# GENN0006_LED_INDICATORS.net
KiCad netlist of a schematic drawn in Altium Designer
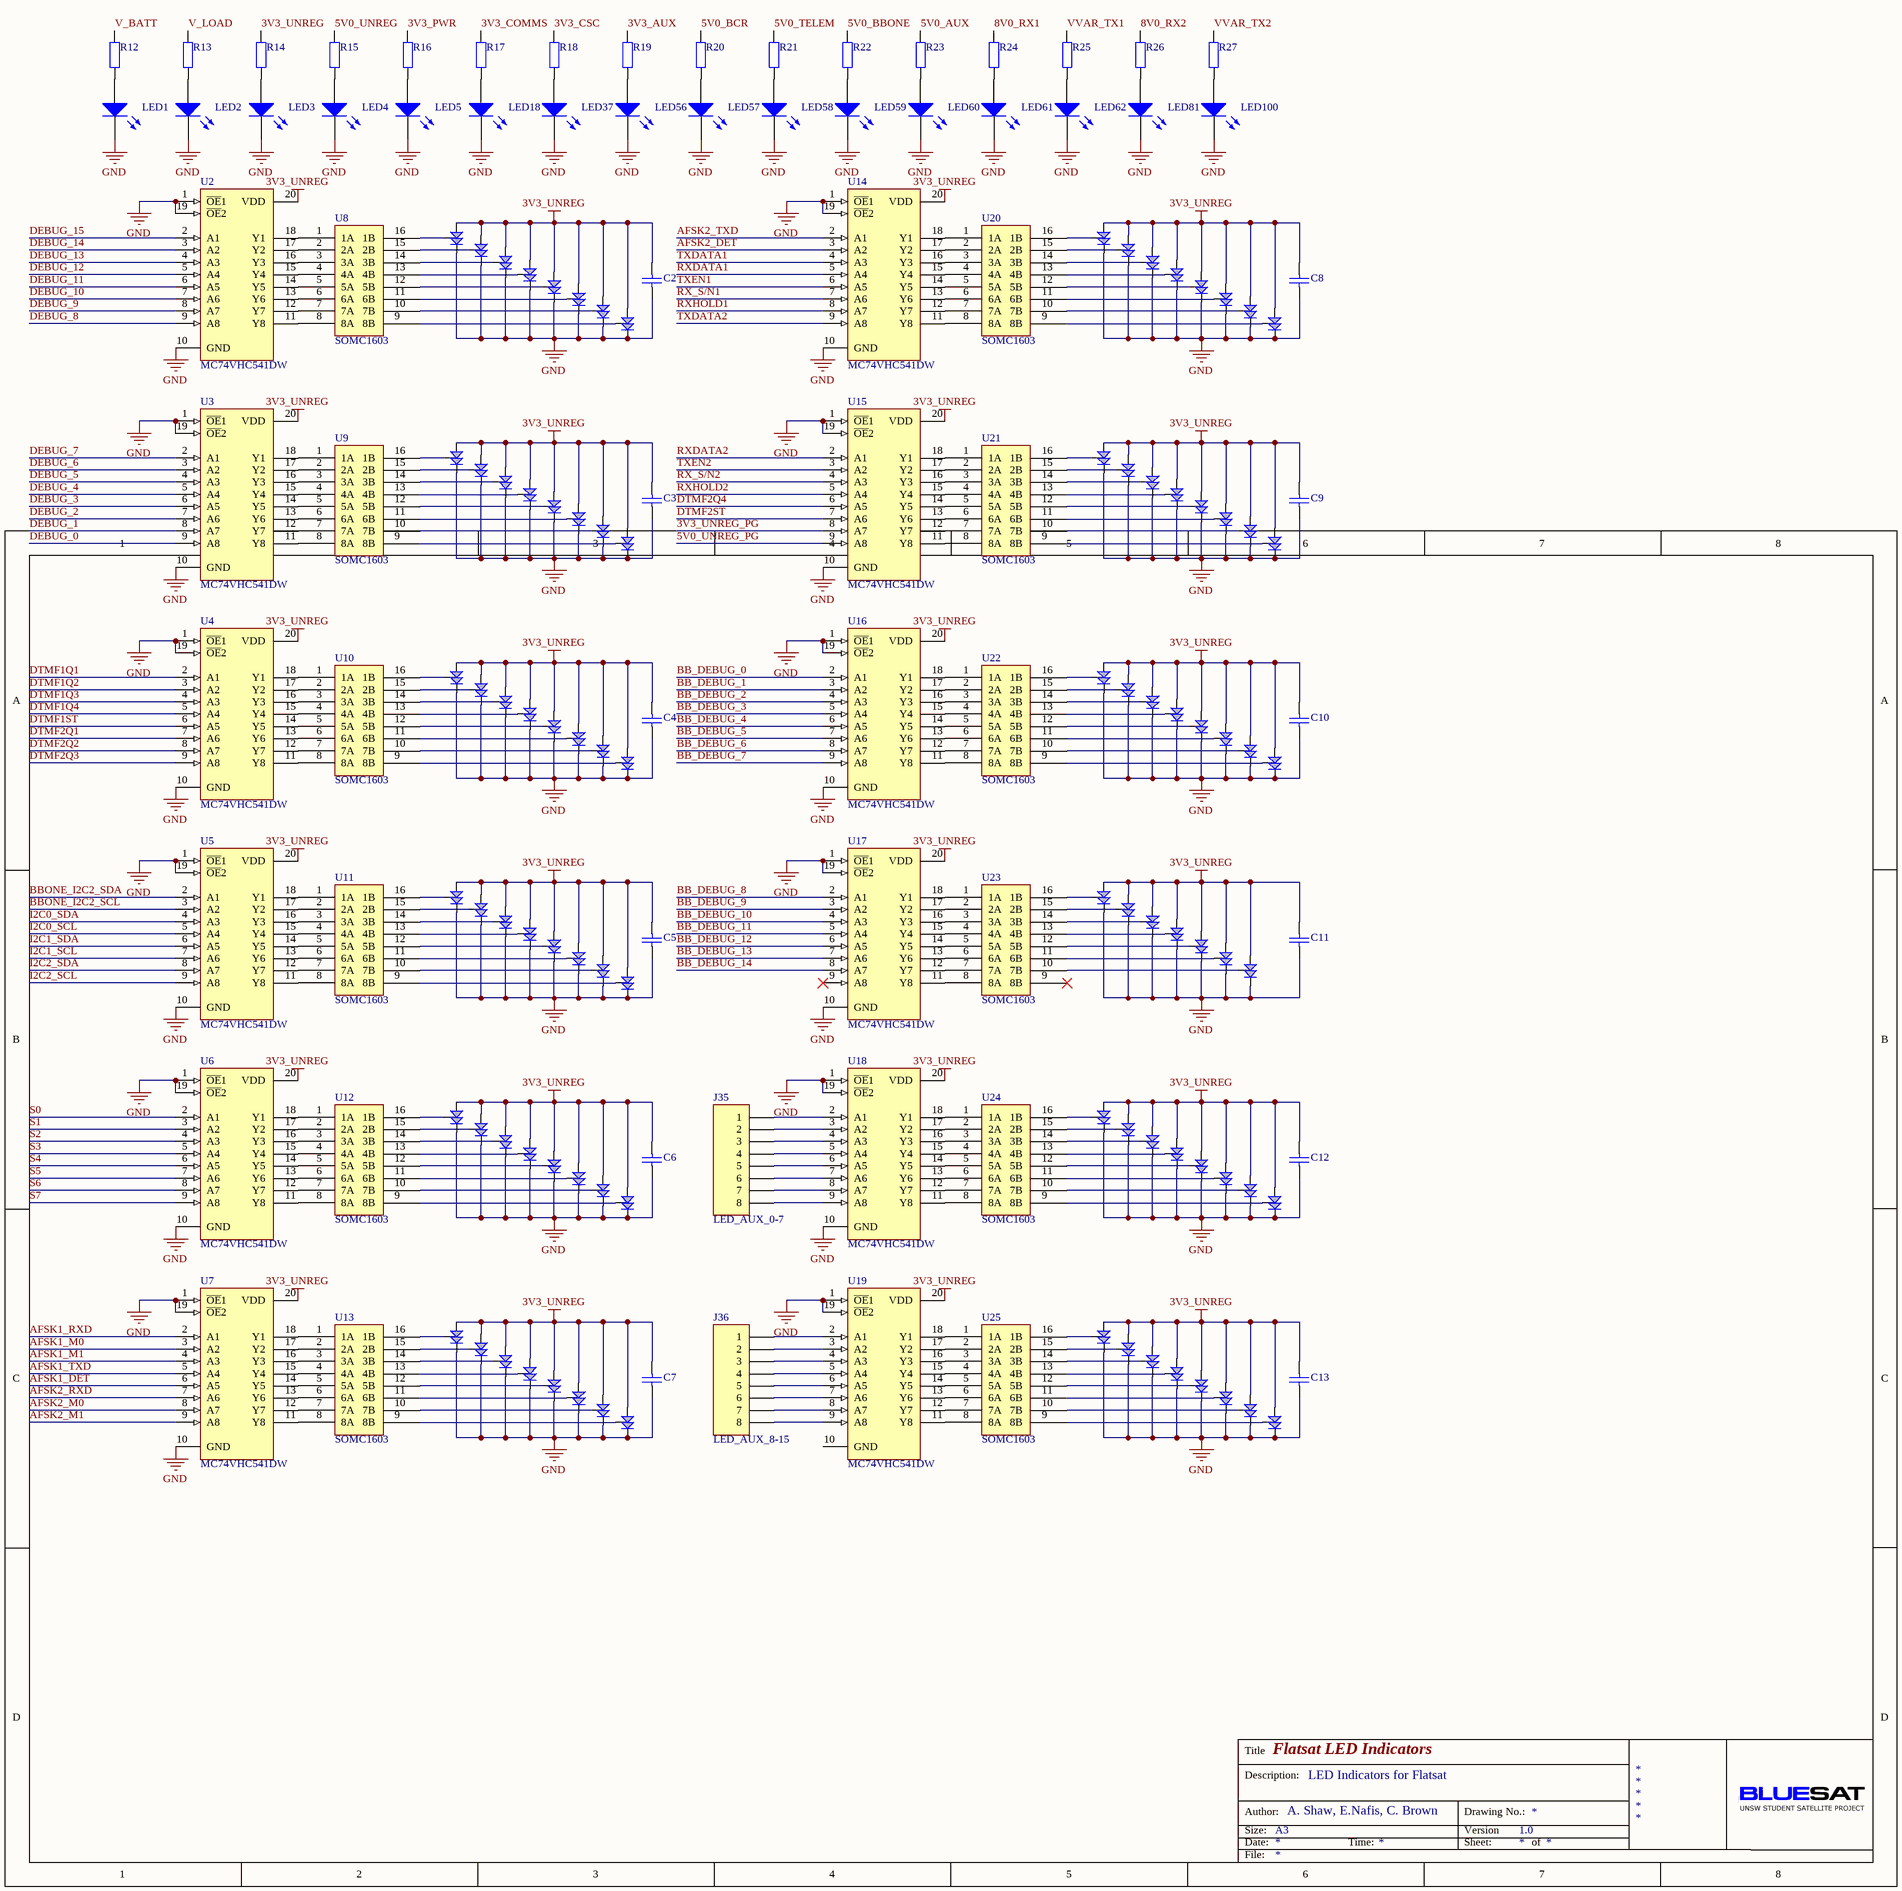
[diagram p0: GENN0006 LED_INDICATORS.SchDoc]

(export (version "E")
  (design (tool "Eeschema 10.0.6"))
  (components
    (comp (ref "C2")
      (value "~")
      (footprint "6-0805_M")
      (description "Capacitor")
      (fields (field (name "PUBLISHER") "Altium Limited"))
      (libsource (lib "Miscellaneous Devices") (part "Cap"))
    )
    (comp (ref "C3")
      (value "~")
      (footprint "6-0805_M")
      (description "Capacitor")
      (fields (field (name "PUBLISHER") "Altium Limited"))
      (libsource (lib "Miscellaneous Devices") (part "Cap"))
    )
    (comp (ref "C4")
      (value "~")
      (footprint "6-0805_M")
      (description "Capacitor")
      (fields (field (name "PUBLISHER") "Altium Limited"))
      (libsource (lib "Miscellaneous Devices") (part "Cap"))
    )
    (comp (ref "C5")
      (value "~")
      (footprint "6-0805_M")
      (description "Capacitor")
      (fields (field (name "PUBLISHER") "Altium Limited"))
      (libsource (lib "Miscellaneous Devices") (part "Cap"))
    )
    (comp (ref "C6")
      (value "~")
      (footprint "6-0805_M")
      (description "Capacitor")
      (fields (field (name "PUBLISHER") "Altium Limited"))
      (libsource (lib "Miscellaneous Devices") (part "Cap"))
    )
    (comp (ref "C7")
      (value "~")
      (footprint "6-0805_M")
      (description "Capacitor")
      (fields (field (name "PUBLISHER") "Altium Limited"))
      (libsource (lib "Miscellaneous Devices") (part "Cap"))
    )
    (comp (ref "C8")
      (value "~")
      (footprint "6-0805_M")
      (description "Capacitor")
      (fields (field (name "PUBLISHER") "Altium Limited"))
      (libsource (lib "Miscellaneous Devices") (part "Cap"))
    )
    (comp (ref "C9")
      (value "~")
      (footprint "6-0805_M")
      (description "Capacitor")
      (fields (field (name "PUBLISHER") "Altium Limited"))
      (libsource (lib "Miscellaneous Devices") (part "Cap"))
    )
    (comp (ref "C10")
      (value "~")
      (footprint "6-0805_M")
      (description "Capacitor")
      (fields (field (name "PUBLISHER") "Altium Limited"))
      (libsource (lib "Miscellaneous Devices") (part "Cap"))
    )
    (comp (ref "C11")
      (value "~")
      (footprint "6-0805_M")
      (description "Capacitor")
      (fields (field (name "PUBLISHER") "Altium Limited"))
      (libsource (lib "Miscellaneous Devices") (part "Cap"))
    )
    (comp (ref "C12")
      (value "~")
      (footprint "6-0805_M")
      (description "Capacitor")
      (fields (field (name "PUBLISHER") "Altium Limited"))
      (libsource (lib "Miscellaneous Devices") (part "Cap"))
    )
    (comp (ref "C13")
      (value "~")
      (footprint "6-0805_M")
      (description "Capacitor")
      (fields (field (name "PUBLISHER") "Altium Limited"))
      (libsource (lib "Miscellaneous Devices") (part "Cap"))
    )
    (comp (ref "J35")
      (value "LED_AUX_0-7")
      (footprint "HDR1X8")
      (description "Header, 8-Pin")
      (fields (field (name "PUBLISHER") "Altium Limited"))
      (libsource (lib "Miscellaneous Connectors") (part "Header 8"))
    )
    (comp (ref "J36")
      (value "LED_AUX_8-15")
      (footprint "HDR1X8")
      (description "Header, 8-Pin")
      (fields (field (name "PUBLISHER") "Altium Limited"))
      (libsource (lib "Miscellaneous Connectors") (part "Header 8"))
    )
    (comp (ref "LED1")
      (value "V_BATT")
      (footprint "6-0805_M")
      (description "Typical INFRARED GaAs LED")
      (fields (field (name "PUBLISHER") "Altium Limited"))
      (libsource (lib "Miscellaneous Devices") (part "LED0"))
    )
    (comp (ref "LED2")
      (value "V_LOAD")
      (footprint "6-0805_M")
      (description "Typical INFRARED GaAs LED")
      (fields (field (name "PUBLISHER") "Altium Limited"))
      (libsource (lib "Miscellaneous Devices") (part "LED0"))
    )
    (comp (ref "LED3")
      (value "3V3_UNREG")
      (footprint "6-0805_M")
      (description "Typical INFRARED GaAs LED")
      (fields (field (name "PUBLISHER") "Altium Limited"))
      (libsource (lib "Miscellaneous Devices") (part "LED0"))
    )
    (comp (ref "LED4")
      (value "5V0_UNREG")
      (footprint "6-0805_M")
      (description "Typical INFRARED GaAs LED")
      (fields (field (name "PUBLISHER") "Altium Limited"))
      (libsource (lib "Miscellaneous Devices") (part "LED0"))
    )
    (comp (ref "LED5")
      (value "3V3_PWR")
      (footprint "6-0805_M")
      (description "Typical INFRARED GaAs LED")
      (fields (field (name "PUBLISHER") "Altium Limited"))
      (libsource (lib "Miscellaneous Devices") (part "LED0"))
    )
    (comp (ref "LED6")
      (value "DEBUG_15")
      (footprint "BIDIRECTIONAL LED")
      (libsource (lib "FlatBoards") (part "BIDIRECTIONAL LED"))
    )
    (comp (ref "LED7")
      (value "DEBUG_7")
      (footprint "BIDIRECTIONAL LED")
      (libsource (lib "FlatBoards") (part "BIDIRECTIONAL LED"))
    )
    (comp (ref "LED8")
      (value "DTMF1Q1")
      (footprint "BIDIRECTIONAL LED")
      (libsource (lib "FlatBoards") (part "BIDIRECTIONAL LED"))
    )
    (comp (ref "LED9")
      (value "DTMF2Q4")
      (footprint "BIDIRECTIONAL LED")
      (libsource (lib "FlatBoards") (part "BIDIRECTIONAL LED"))
    )
    (comp (ref "LED10")
      (value "S0")
      (footprint "BIDIRECTIONAL LED")
      (libsource (lib "FlatBoards") (part "BIDIRECTIONAL LED"))
    )
    (comp (ref "LED11")
      (value "AFSK1_RXD")
      (footprint "BIDIRECTIONAL LED")
      (libsource (lib "FlatBoards") (part "BIDIRECTIONAL LED"))
    )
    (comp (ref "LED12")
      (value "DEBUG_14")
      (footprint "BIDIRECTIONAL LED")
      (libsource (lib "FlatBoards") (part "BIDIRECTIONAL LED"))
    )
    (comp (ref "LED13")
      (value "DEBUG_6")
      (footprint "BIDIRECTIONAL LED")
      (libsource (lib "FlatBoards") (part "BIDIRECTIONAL LED"))
    )
    (comp (ref "LED14")
      (value "DTMF1Q2")
      (footprint "BIDIRECTIONAL LED")
      (libsource (lib "FlatBoards") (part "BIDIRECTIONAL LED"))
    )
    (comp (ref "LED15")
      (value "DTMF2ST")
      (footprint "BIDIRECTIONAL LED")
      (libsource (lib "FlatBoards") (part "BIDIRECTIONAL LED"))
    )
    (comp (ref "LED16")
      (value "S1")
      (footprint "BIDIRECTIONAL LED")
      (libsource (lib "FlatBoards") (part "BIDIRECTIONAL LED"))
    )
    (comp (ref "LED17")
      (value "AFSK1_M0")
      (footprint "BIDIRECTIONAL LED")
      (libsource (lib "FlatBoards") (part "BIDIRECTIONAL LED"))
    )
    (comp (ref "LED18")
      (value "3V3_COMMS")
      (footprint "6-0805_M")
      (description "Typical INFRARED GaAs LED")
      (fields (field (name "PUBLISHER") "Altium Limited"))
      (libsource (lib "Miscellaneous Devices") (part "LED0"))
    )
    (comp (ref "LED19")
      (value "DEBUG_13")
      (footprint "BIDIRECTIONAL LED")
      (libsource (lib "FlatBoards") (part "BIDIRECTIONAL LED"))
    )
    (comp (ref "LED20")
      (value "DEBUG_5")
      (footprint "BIDIRECTIONAL LED")
      (libsource (lib "FlatBoards") (part "BIDIRECTIONAL LED"))
    )
    (comp (ref "LED21")
      (value "DTMF1Q3")
      (footprint "BIDIRECTIONAL LED")
      (libsource (lib "FlatBoards") (part "BIDIRECTIONAL LED"))
    )
    (comp (ref "LED22")
      (value "I2C0_SDA")
      (footprint "BIDIRECTIONAL LED")
      (libsource (lib "FlatBoards") (part "BIDIRECTIONAL LED"))
    )
    (comp (ref "LED23")
      (value "S2")
      (footprint "BIDIRECTIONAL LED")
      (libsource (lib "FlatBoards") (part "BIDIRECTIONAL LED"))
    )
    (comp (ref "LED24")
      (value "AFSK1_M1")
      (footprint "BIDIRECTIONAL LED")
      (libsource (lib "FlatBoards") (part "BIDIRECTIONAL LED"))
    )
    (comp (ref "LED25")
      (value "DEBUG_12")
      (footprint "BIDIRECTIONAL LED")
      (libsource (lib "FlatBoards") (part "BIDIRECTIONAL LED"))
    )
    (comp (ref "LED26")
      (value "DEBUG_4")
      (footprint "BIDIRECTIONAL LED")
      (libsource (lib "FlatBoards") (part "BIDIRECTIONAL LED"))
    )
    (comp (ref "LED27")
      (value "DTMF1Q4")
      (footprint "BIDIRECTIONAL LED")
      (libsource (lib "FlatBoards") (part "BIDIRECTIONAL LED"))
    )
    (comp (ref "LED28")
      (value "I2C0_SCL")
      (footprint "BIDIRECTIONAL LED")
      (libsource (lib "FlatBoards") (part "BIDIRECTIONAL LED"))
    )
    (comp (ref "LED29")
      (value "S3")
      (footprint "BIDIRECTIONAL LED")
      (libsource (lib "FlatBoards") (part "BIDIRECTIONAL LED"))
    )
    (comp (ref "LED30")
      (value "AFSK1_TXD")
      (footprint "BIDIRECTIONAL LED")
      (libsource (lib "FlatBoards") (part "BIDIRECTIONAL LED"))
    )
    (comp (ref "LED31")
      (value "DEBUG_11")
      (footprint "BIDIRECTIONAL LED")
      (libsource (lib "FlatBoards") (part "BIDIRECTIONAL LED"))
    )
    (comp (ref "LED32")
      (value "DEBUG_3")
      (footprint "BIDIRECTIONAL LED")
      (libsource (lib "FlatBoards") (part "BIDIRECTIONAL LED"))
    )
    (comp (ref "LED33")
      (value "DTMF1ST")
      (footprint "BIDIRECTIONAL LED")
      (libsource (lib "FlatBoards") (part "BIDIRECTIONAL LED"))
    )
    (comp (ref "LED34")
      (value "I2C1_SDA")
      (footprint "BIDIRECTIONAL LED")
      (libsource (lib "FlatBoards") (part "BIDIRECTIONAL LED"))
    )
    (comp (ref "LED35")
      (value "S4")
      (footprint "BIDIRECTIONAL LED")
      (libsource (lib "FlatBoards") (part "BIDIRECTIONAL LED"))
    )
    (comp (ref "LED36")
      (value "AFSK1_DET")
      (footprint "BIDIRECTIONAL LED")
      (libsource (lib "FlatBoards") (part "BIDIRECTIONAL LED"))
    )
    (comp (ref "LED37")
      (value "3V3_CSC")
      (footprint "6-0805_M")
      (description "Typical INFRARED GaAs LED")
      (fields (field (name "PUBLISHER") "Altium Limited"))
      (libsource (lib "Miscellaneous Devices") (part "LED0"))
    )
    (comp (ref "LED38")
      (value "DEBUG_10")
      (footprint "BIDIRECTIONAL LED")
      (libsource (lib "FlatBoards") (part "BIDIRECTIONAL LED"))
    )
    (comp (ref "LED39")
      (value "DEBUG_2")
      (footprint "BIDIRECTIONAL LED")
      (libsource (lib "FlatBoards") (part "BIDIRECTIONAL LED"))
    )
    (comp (ref "LED40")
      (value "DTMF2Q1")
      (footprint "BIDIRECTIONAL LED")
      (libsource (lib "FlatBoards") (part "BIDIRECTIONAL LED"))
    )
    (comp (ref "LED41")
      (value "I2C1_SCL")
      (footprint "BIDIRECTIONAL LED")
      (libsource (lib "FlatBoards") (part "BIDIRECTIONAL LED"))
    )
    (comp (ref "LED42")
      (value "S5")
      (footprint "BIDIRECTIONAL LED")
      (libsource (lib "FlatBoards") (part "BIDIRECTIONAL LED"))
    )
    (comp (ref "LED43")
      (value "AFSK2_RXD")
      (footprint "BIDIRECTIONAL LED")
      (libsource (lib "FlatBoards") (part "BIDIRECTIONAL LED"))
    )
    (comp (ref "LED44")
      (value "DEBUG_9")
      (footprint "BIDIRECTIONAL LED")
      (libsource (lib "FlatBoards") (part "BIDIRECTIONAL LED"))
    )
    (comp (ref "LED45")
      (value "DEBUG_1")
      (footprint "BIDIRECTIONAL LED")
      (libsource (lib "FlatBoards") (part "BIDIRECTIONAL LED"))
    )
    (comp (ref "LED46")
      (value "DTMF2Q2")
      (footprint "BIDIRECTIONAL LED")
      (libsource (lib "FlatBoards") (part "BIDIRECTIONAL LED"))
    )
    (comp (ref "LED47")
      (value "I2C2_SDA")
      (footprint "BIDIRECTIONAL LED")
      (libsource (lib "FlatBoards") (part "BIDIRECTIONAL LED"))
    )
    (comp (ref "LED48")
      (value "S6")
      (footprint "BIDIRECTIONAL LED")
      (libsource (lib "FlatBoards") (part "BIDIRECTIONAL LED"))
    )
    (comp (ref "LED49")
      (value "AFSK2_M0")
      (footprint "BIDIRECTIONAL LED")
      (libsource (lib "FlatBoards") (part "BIDIRECTIONAL LED"))
    )
    (comp (ref "LED50")
      (value "DEBUG_8")
      (footprint "BIDIRECTIONAL LED")
      (libsource (lib "FlatBoards") (part "BIDIRECTIONAL LED"))
    )
    (comp (ref "LED51")
      (value "DEBUG_0")
      (footprint "BIDIRECTIONAL LED")
      (libsource (lib "FlatBoards") (part "BIDIRECTIONAL LED"))
    )
    (comp (ref "LED52")
      (value "DTMF2Q3")
      (footprint "BIDIRECTIONAL LED")
      (libsource (lib "FlatBoards") (part "BIDIRECTIONAL LED"))
    )
    (comp (ref "LED53")
      (value "I2C2_SCL")
      (footprint "BIDIRECTIONAL LED")
      (libsource (lib "FlatBoards") (part "BIDIRECTIONAL LED"))
    )
    (comp (ref "LED54")
      (value "S7")
      (footprint "BIDIRECTIONAL LED")
      (libsource (lib "FlatBoards") (part "BIDIRECTIONAL LED"))
    )
    (comp (ref "LED55")
      (value "AFSK2_M1")
      (footprint "BIDIRECTIONAL LED")
      (libsource (lib "FlatBoards") (part "BIDIRECTIONAL LED"))
    )
    (comp (ref "LED56")
      (value "3V3_AUX")
      (footprint "6-0805_M")
      (description "Typical INFRARED GaAs LED")
      (fields (field (name "PUBLISHER") "Altium Limited"))
      (libsource (lib "Miscellaneous Devices") (part "LED0"))
    )
    (comp (ref "LED57")
      (value "5V0_BCR")
      (footprint "6-0805_M")
      (description "Typical INFRARED GaAs LED")
      (fields (field (name "PUBLISHER") "Altium Limited"))
      (libsource (lib "Miscellaneous Devices") (part "LED0"))
    )
    (comp (ref "LED58")
      (value "5V0_TELEM")
      (footprint "6-0805_M")
      (description "Typical INFRARED GaAs LED")
      (fields (field (name "PUBLISHER") "Altium Limited"))
      (libsource (lib "Miscellaneous Devices") (part "LED0"))
    )
    (comp (ref "LED59")
      (value "5V0_BBONE")
      (footprint "6-0805_M")
      (description "Typical INFRARED GaAs LED")
      (fields (field (name "PUBLISHER") "Altium Limited"))
      (libsource (lib "Miscellaneous Devices") (part "LED0"))
    )
    (comp (ref "LED60")
      (value "5V0_AUX")
      (footprint "6-0805_M")
      (description "Typical INFRARED GaAs LED")
      (fields (field (name "PUBLISHER") "Altium Limited"))
      (libsource (lib "Miscellaneous Devices") (part "LED0"))
    )
    (comp (ref "LED61")
      (value "8V0_RX1")
      (footprint "6-0805_M")
      (description "Typical INFRARED GaAs LED")
      (fields (field (name "PUBLISHER") "Altium Limited"))
      (libsource (lib "Miscellaneous Devices") (part "LED0"))
    )
    (comp (ref "LED62")
      (value "VVAR_TX1")
      (footprint "6-0805_M")
      (description "Typical INFRARED GaAs LED")
      (fields (field (name "PUBLISHER") "Altium Limited"))
      (libsource (lib "Miscellaneous Devices") (part "LED0"))
    )
    (comp (ref "LED63")
      (value "AFSK2_TXD")
      (footprint "BIDIRECTIONAL LED")
      (libsource (lib "FlatBoards") (part "BIDIRECTIONAL LED"))
    )
    (comp (ref "LED64")
      (value "RXDATA2")
      (footprint "BIDIRECTIONAL LED")
      (libsource (lib "FlatBoards") (part "BIDIRECTIONAL LED"))
    )
    (comp (ref "LED65")
      (value "BB_DEBUG_0")
      (footprint "BIDIRECTIONAL LED")
      (libsource (lib "FlatBoards") (part "BIDIRECTIONAL LED"))
    )
    (comp (ref "LED66")
      (value "BB_DEBUG_8")
      (footprint "BIDIRECTIONAL LED")
      (libsource (lib "FlatBoards") (part "BIDIRECTIONAL LED"))
    )
    (comp (ref "LED67")
      (value "LED_AUX_0")
      (footprint "BIDIRECTIONAL LED")
      (libsource (lib "FlatBoards") (part "BIDIRECTIONAL LED"))
    )
    (comp (ref "LED68")
      (value "LED_AUX_8")
      (footprint "BIDIRECTIONAL LED")
      (libsource (lib "FlatBoards") (part "BIDIRECTIONAL LED"))
    )
    (comp (ref "LED69")
      (value "AFSK2_DET")
      (footprint "BIDIRECTIONAL LED")
      (libsource (lib "FlatBoards") (part "BIDIRECTIONAL LED"))
    )
    (comp (ref "LED70")
      (value "TXEN2")
      (footprint "BIDIRECTIONAL LED")
      (libsource (lib "FlatBoards") (part "BIDIRECTIONAL LED"))
    )
    (comp (ref "LED71")
      (value "BB_DEBUG_1")
      (footprint "BIDIRECTIONAL LED")
      (libsource (lib "FlatBoards") (part "BIDIRECTIONAL LED"))
    )
    (comp (ref "LED72")
      (value "BB_DEBUG_9")
      (footprint "BIDIRECTIONAL LED")
      (libsource (lib "FlatBoards") (part "BIDIRECTIONAL LED"))
    )
    (comp (ref "LED73")
      (value "LED_AUX_1")
      (footprint "BIDIRECTIONAL LED")
      (libsource (lib "FlatBoards") (part "BIDIRECTIONAL LED"))
    )
    (comp (ref "LED74")
      (value "LED_AUX_9")
      (footprint "BIDIRECTIONAL LED")
      (libsource (lib "FlatBoards") (part "BIDIRECTIONAL LED"))
    )
    (comp (ref "LED75")
      (value "TXDATA1")
      (footprint "BIDIRECTIONAL LED")
      (libsource (lib "FlatBoards") (part "BIDIRECTIONAL LED"))
    )
    (comp (ref "LED76")
      (value "RX_S/N2")
      (footprint "BIDIRECTIONAL LED")
      (libsource (lib "FlatBoards") (part "BIDIRECTIONAL LED"))
    )
    (comp (ref "LED77")
      (value "BB_DEBUG_2")
      (footprint "BIDIRECTIONAL LED")
      (libsource (lib "FlatBoards") (part "BIDIRECTIONAL LED"))
    )
    (comp (ref "LED78")
      (value "BB_DEBUG_10")
      (footprint "BIDIRECTIONAL LED")
      (libsource (lib "FlatBoards") (part "BIDIRECTIONAL LED"))
    )
    (comp (ref "LED79")
      (value "LED_AUX_2")
      (footprint "BIDIRECTIONAL LED")
      (libsource (lib "FlatBoards") (part "BIDIRECTIONAL LED"))
    )
    (comp (ref "LED80")
      (value "LED_AUX_10")
      (footprint "BIDIRECTIONAL LED")
      (libsource (lib "FlatBoards") (part "BIDIRECTIONAL LED"))
    )
    (comp (ref "LED81")
      (value "8V0_RX2")
      (footprint "6-0805_M")
      (description "Typical INFRARED GaAs LED")
      (fields (field (name "PUBLISHER") "Altium Limited"))
      (libsource (lib "Miscellaneous Devices") (part "LED0"))
    )
    (comp (ref "LED82")
      (value "RXDATA1")
      (footprint "BIDIRECTIONAL LED")
      (libsource (lib "FlatBoards") (part "BIDIRECTIONAL LED"))
    )
    (comp (ref "LED83")
      (value "RXHOLD2")
      (footprint "BIDIRECTIONAL LED")
      (libsource (lib "FlatBoards") (part "BIDIRECTIONAL LED"))
    )
    (comp (ref "LED84")
      (value "BB_DEBUG_3")
      (footprint "BIDIRECTIONAL LED")
      (libsource (lib "FlatBoards") (part "BIDIRECTIONAL LED"))
    )
    (comp (ref "LED85")
      (value "BB_DEBUG_11")
      (footprint "BIDIRECTIONAL LED")
      (libsource (lib "FlatBoards") (part "BIDIRECTIONAL LED"))
    )
    (comp (ref "LED86")
      (value "LED_AUX_3")
      (footprint "BIDIRECTIONAL LED")
      (libsource (lib "FlatBoards") (part "BIDIRECTIONAL LED"))
    )
    (comp (ref "LED87")
      (value "LED_AUX_11")
      (footprint "BIDIRECTIONAL LED")
      (libsource (lib "FlatBoards") (part "BIDIRECTIONAL LED"))
    )
    (comp (ref "LED88")
      (value "TXEN1")
      (footprint "BIDIRECTIONAL LED")
      (libsource (lib "FlatBoards") (part "BIDIRECTIONAL LED"))
    )
    (comp (ref "LED89")
      (value "BBONE_I2C2_SDA")
      (footprint "BIDIRECTIONAL LED")
      (libsource (lib "FlatBoards") (part "BIDIRECTIONAL LED"))
    )
    (comp (ref "LED90")
      (value "BB_DEBUG_4")
      (footprint "BIDIRECTIONAL LED")
      (libsource (lib "FlatBoards") (part "BIDIRECTIONAL LED"))
    )
    (comp (ref "LED91")
      (value "BB_DEBUG_12")
      (footprint "BIDIRECTIONAL LED")
      (libsource (lib "FlatBoards") (part "BIDIRECTIONAL LED"))
    )
    (comp (ref "LED92")
      (value "LED_AUX_4")
      (footprint "BIDIRECTIONAL LED")
      (libsource (lib "FlatBoards") (part "BIDIRECTIONAL LED"))
    )
    (comp (ref "LED93")
      (value "LED_AUX_12")
      (footprint "BIDIRECTIONAL LED")
      (libsource (lib "FlatBoards") (part "BIDIRECTIONAL LED"))
    )
    (comp (ref "LED94")
      (value "RX_S/N1")
      (footprint "BIDIRECTIONAL LED")
      (libsource (lib "FlatBoards") (part "BIDIRECTIONAL LED"))
    )
    (comp (ref "LED95")
      (value "BBONE_I2C2_SCL")
      (footprint "BIDIRECTIONAL LED")
      (libsource (lib "FlatBoards") (part "BIDIRECTIONAL LED"))
    )
    (comp (ref "LED96")
      (value "BB_DEBUG_5")
      (footprint "BIDIRECTIONAL LED")
      (libsource (lib "FlatBoards") (part "BIDIRECTIONAL LED"))
    )
    (comp (ref "LED97")
      (value "BB_DEBUG_13")
      (footprint "BIDIRECTIONAL LED")
      (libsource (lib "FlatBoards") (part "BIDIRECTIONAL LED"))
    )
    (comp (ref "LED98")
      (value "LED_AUX_5")
      (footprint "BIDIRECTIONAL LED")
      (libsource (lib "FlatBoards") (part "BIDIRECTIONAL LED"))
    )
    (comp (ref "LED99")
      (value "LED_AUX_13")
      (footprint "BIDIRECTIONAL LED")
      (libsource (lib "FlatBoards") (part "BIDIRECTIONAL LED"))
    )
    (comp (ref "LED100")
      (value "VVAR_TX2")
      (footprint "6-0805_M")
      (description "Typical INFRARED GaAs LED")
      (fields (field (name "PUBLISHER") "Altium Limited"))
      (libsource (lib "Miscellaneous Devices") (part "LED0"))
    )
    (comp (ref "LED101")
      (value "RXHOLD1")
      (footprint "BIDIRECTIONAL LED")
      (libsource (lib "FlatBoards") (part "BIDIRECTIONAL LED"))
    )
    (comp (ref "LED102")
      (value "3V3_UNREG_PG")
      (footprint "BIDIRECTIONAL LED")
      (libsource (lib "FlatBoards") (part "BIDIRECTIONAL LED"))
    )
    (comp (ref "LED103")
      (value "BB_DEBUG_6")
      (footprint "BIDIRECTIONAL LED")
      (libsource (lib "FlatBoards") (part "BIDIRECTIONAL LED"))
    )
    (comp (ref "LED104")
      (value "BB_DEBUG_14")
      (footprint "BIDIRECTIONAL LED")
      (libsource (lib "FlatBoards") (part "BIDIRECTIONAL LED"))
    )
    (comp (ref "LED105")
      (value "LED_AUX_6")
      (footprint "BIDIRECTIONAL LED")
      (libsource (lib "FlatBoards") (part "BIDIRECTIONAL LED"))
    )
    (comp (ref "LED106")
      (value "LED_AUX_14")
      (footprint "BIDIRECTIONAL LED")
      (libsource (lib "FlatBoards") (part "BIDIRECTIONAL LED"))
    )
    (comp (ref "LED107")
      (value "TXDATA2")
      (footprint "BIDIRECTIONAL LED")
      (libsource (lib "FlatBoards") (part "BIDIRECTIONAL LED"))
    )
    (comp (ref "LED108")
      (value "5V0_UNREG_PG")
      (footprint "BIDIRECTIONAL LED")
      (libsource (lib "FlatBoards") (part "BIDIRECTIONAL LED"))
    )
    (comp (ref "LED109")
      (value "BB_DEBUG_7")
      (footprint "BIDIRECTIONAL LED")
      (libsource (lib "FlatBoards") (part "BIDIRECTIONAL LED"))
    )
    (comp (ref "LED111")
      (value "LED_AUX_7")
      (footprint "BIDIRECTIONAL LED")
      (libsource (lib "FlatBoards") (part "BIDIRECTIONAL LED"))
    )
    (comp (ref "LED112")
      (value "LED_AUX_15")
      (footprint "BIDIRECTIONAL LED")
      (libsource (lib "FlatBoards") (part "BIDIRECTIONAL LED"))
    )
    (comp (ref "R12")
      (value "Res2")
      (footprint "6-0805_M")
      (description "Resistor")
      (fields (field (name "PUBLISHER") "Altium Limited"))
      (libsource (lib "Miscellaneous Devices") (part "Res2"))
    )
    (comp (ref "R13")
      (value "Res2")
      (footprint "6-0805_M")
      (description "Resistor")
      (fields (field (name "PUBLISHER") "Altium Limited"))
      (libsource (lib "Miscellaneous Devices") (part "Res2"))
    )
    (comp (ref "R14")
      (value "Res2")
      (footprint "6-0805_M")
      (description "Resistor")
      (fields (field (name "PUBLISHER") "Altium Limited"))
      (libsource (lib "Miscellaneous Devices") (part "Res2"))
    )
    (comp (ref "R15")
      (value "Res2")
      (footprint "6-0805_M")
      (description "Resistor")
      (fields (field (name "PUBLISHER") "Altium Limited"))
      (libsource (lib "Miscellaneous Devices") (part "Res2"))
    )
    (comp (ref "R16")
      (value "Res2")
      (footprint "6-0805_M")
      (description "Resistor")
      (fields (field (name "PUBLISHER") "Altium Limited"))
      (libsource (lib "Miscellaneous Devices") (part "Res2"))
    )
    (comp (ref "R17")
      (value "Res2")
      (footprint "6-0805_M")
      (description "Resistor")
      (fields (field (name "PUBLISHER") "Altium Limited"))
      (libsource (lib "Miscellaneous Devices") (part "Res2"))
    )
    (comp (ref "R18")
      (value "Res2")
      (footprint "6-0805_M")
      (description "Resistor")
      (fields (field (name "PUBLISHER") "Altium Limited"))
      (libsource (lib "Miscellaneous Devices") (part "Res2"))
    )
    (comp (ref "R19")
      (value "Res2")
      (footprint "6-0805_M")
      (description "Resistor")
      (fields (field (name "PUBLISHER") "Altium Limited"))
      (libsource (lib "Miscellaneous Devices") (part "Res2"))
    )
    (comp (ref "R20")
      (value "Res2")
      (footprint "6-0805_M")
      (description "Resistor")
      (fields (field (name "PUBLISHER") "Altium Limited"))
      (libsource (lib "Miscellaneous Devices") (part "Res2"))
    )
    (comp (ref "R21")
      (value "Res2")
      (footprint "6-0805_M")
      (description "Resistor")
      (fields (field (name "PUBLISHER") "Altium Limited"))
      (libsource (lib "Miscellaneous Devices") (part "Res2"))
    )
    (comp (ref "R22")
      (value "Res2")
      (footprint "6-0805_M")
      (description "Resistor")
      (fields (field (name "PUBLISHER") "Altium Limited"))
      (libsource (lib "Miscellaneous Devices") (part "Res2"))
    )
    (comp (ref "R23")
      (value "Res2")
      (footprint "6-0805_M")
      (description "Resistor")
      (fields (field (name "PUBLISHER") "Altium Limited"))
      (libsource (lib "Miscellaneous Devices") (part "Res2"))
    )
    (comp (ref "R24")
      (value "Res2")
      (footprint "6-0805_M")
      (description "Resistor")
      (fields (field (name "PUBLISHER") "Altium Limited"))
      (libsource (lib "Miscellaneous Devices") (part "Res2"))
    )
    (comp (ref "R25")
      (value "Res2")
      (footprint "6-0805_M")
      (description "Resistor")
      (fields (field (name "PUBLISHER") "Altium Limited"))
      (libsource (lib "Miscellaneous Devices") (part "Res2"))
    )
    (comp (ref "R26")
      (value "Res2")
      (footprint "6-0805_M")
      (description "Resistor")
      (fields (field (name "PUBLISHER") "Altium Limited"))
      (libsource (lib "Miscellaneous Devices") (part "Res2"))
    )
    (comp (ref "R27")
      (value "Res2")
      (footprint "6-0805_M")
      (description "Resistor")
      (fields (field (name "PUBLISHER") "Altium Limited"))
      (libsource (lib "Miscellaneous Devices") (part "Res2"))
    )
    (comp (ref "U2")
      (value "MC74VHC541DW")
      (footprint "751D-04_M")
      (description "Octal Bus Buffer")
      (fields (field (name "PUBLISHER") "Altium Limited"))
      (libsource (lib "FlatBoards") (part "MC74VHC541DW"))
    )
    (comp (ref "U3")
      (value "MC74VHC541DW")
      (footprint "751D-04_M")
      (description "Octal Bus Buffer")
      (fields (field (name "PUBLISHER") "Altium Limited"))
      (libsource (lib "FlatBoards") (part "MC74VHC541DW"))
    )
    (comp (ref "U4")
      (value "MC74VHC541DW")
      (footprint "751D-04_M")
      (description "Octal Bus Buffer")
      (fields (field (name "PUBLISHER") "Altium Limited"))
      (libsource (lib "FlatBoards") (part "MC74VHC541DW"))
    )
    (comp (ref "U5")
      (value "MC74VHC541DW")
      (footprint "751D-04_M")
      (description "Octal Bus Buffer")
      (fields (field (name "PUBLISHER") "Altium Limited"))
      (libsource (lib "FlatBoards") (part "MC74VHC541DW"))
    )
    (comp (ref "U6")
      (value "MC74VHC541DW")
      (footprint "751D-04_M")
      (description "Octal Bus Buffer")
      (fields (field (name "PUBLISHER") "Altium Limited"))
      (libsource (lib "FlatBoards") (part "MC74VHC541DW"))
    )
    (comp (ref "U7")
      (value "MC74VHC541DW")
      (footprint "751D-04_M")
      (description "Octal Bus Buffer")
      (fields (field (name "PUBLISHER") "Altium Limited"))
      (libsource (lib "FlatBoards") (part "MC74VHC541DW"))
    )
    (comp (ref "U8")
      (value "SOMC1603")
      (footprint "SOMC1603")
      (libsource (lib "FlatBoards") (part "SOMC1603"))
    )
    (comp (ref "U9")
      (value "SOMC1603")
      (footprint "SOMC1603")
      (libsource (lib "FlatBoards") (part "SOMC1603"))
    )
    (comp (ref "U10")
      (value "SOMC1603")
      (footprint "SOMC1603")
      (libsource (lib "FlatBoards") (part "SOMC1603"))
    )
    (comp (ref "U11")
      (value "SOMC1603")
      (footprint "SOMC1603")
      (libsource (lib "FlatBoards") (part "SOMC1603"))
    )
    (comp (ref "U12")
      (value "SOMC1603")
      (footprint "SOMC1603")
      (libsource (lib "FlatBoards") (part "SOMC1603"))
    )
    (comp (ref "U13")
      (value "SOMC1603")
      (footprint "SOMC1603")
      (libsource (lib "FlatBoards") (part "SOMC1603"))
    )
    (comp (ref "U14")
      (value "MC74VHC541DW")
      (footprint "751D-04_M")
      (description "Octal Bus Buffer")
      (fields (field (name "PUBLISHER") "Altium Limited"))
      (libsource (lib "FlatBoards") (part "MC74VHC541DW"))
    )
    (comp (ref "U15")
      (value "MC74VHC541DW")
      (footprint "751D-04_M")
      (description "Octal Bus Buffer")
      (fields (field (name "PUBLISHER") "Altium Limited"))
      (libsource (lib "FlatBoards") (part "MC74VHC541DW"))
    )
    (comp (ref "U16")
      (value "MC74VHC541DW")
      (footprint "751D-04_M")
      (description "Octal Bus Buffer")
      (fields (field (name "PUBLISHER") "Altium Limited"))
      (libsource (lib "FlatBoards") (part "MC74VHC541DW"))
    )
    (comp (ref "U17")
      (value "MC74VHC541DW")
      (footprint "751D-04_M")
      (description "Octal Bus Buffer")
      (fields (field (name "PUBLISHER") "Altium Limited"))
      (libsource (lib "FlatBoards") (part "MC74VHC541DW"))
    )
    (comp (ref "U18")
      (value "MC74VHC541DW")
      (footprint "751D-04_M")
      (description "Octal Bus Buffer")
      (fields (field (name "PUBLISHER") "Altium Limited"))
      (libsource (lib "FlatBoards") (part "MC74VHC541DW"))
    )
    (comp (ref "U19")
      (value "MC74VHC541DW")
      (footprint "751D-04_M")
      (description "Octal Bus Buffer")
      (fields (field (name "PUBLISHER") "Altium Limited"))
      (libsource (lib "FlatBoards") (part "MC74VHC541DW"))
    )
    (comp (ref "U20")
      (value "SOMC1603")
      (footprint "SOMC1603")
      (libsource (lib "FlatBoards") (part "SOMC1603"))
    )
    (comp (ref "U21")
      (value "SOMC1603")
      (footprint "SOMC1603")
      (libsource (lib "FlatBoards") (part "SOMC1603"))
    )
    (comp (ref "U22")
      (value "SOMC1603")
      (footprint "SOMC1603")
      (libsource (lib "FlatBoards") (part "SOMC1603"))
    )
    (comp (ref "U23")
      (value "SOMC1603")
      (footprint "SOMC1603")
      (libsource (lib "FlatBoards") (part "SOMC1603"))
    )
    (comp (ref "U24")
      (value "SOMC1603")
      (footprint "SOMC1603")
      (libsource (lib "FlatBoards") (part "SOMC1603"))
    )
    (comp (ref "U25")
      (value "SOMC1603")
      (footprint "SOMC1603")
      (libsource (lib "FlatBoards") (part "SOMC1603"))
    )
  )
  (nets
    (net (code "1") (name "/3V3_AUX") (class "Default")
      (node (ref "R19") (pin "2") (pinfunction "2_2") (pintype "passive"))
    )
    (net (code "2") (name "/3V3_COMMS") (class "Default")
      (node (ref "R17") (pin "2") (pinfunction "2_2") (pintype "passive"))
    )
    (net (code "3") (name "/3V3_CSC") (class "Default")
      (node (ref "R18") (pin "2") (pinfunction "2_2") (pintype "passive"))
    )
    (net (code "4") (name "/3V3_PWR") (class "Default")
      (node (ref "R16") (pin "2") (pinfunction "2_2") (pintype "passive"))
    )
    (net (code "5") (name "/3V3_UNREG_PG") (class "Default")
      (node (ref "U15") (pin "8") (pinfunction "A7_8") (pintype "input"))
    )
    (net (code "6") (name "/5V0_AUX") (class "Default")
      (node (ref "R23") (pin "2") (pinfunction "2_2") (pintype "passive"))
    )
    (net (code "7") (name "/5V0_BBONE") (class "Default")
      (node (ref "R22") (pin "2") (pinfunction "2_2") (pintype "passive"))
    )
    (net (code "8") (name "/5V0_BCR") (class "Default")
      (node (ref "R20") (pin "2") (pinfunction "2_2") (pintype "passive"))
    )
    (net (code "9") (name "/5V0_TELEM") (class "Default")
      (node (ref "R21") (pin "2") (pinfunction "2_2") (pintype "passive"))
    )
    (net (code "10") (name "/5V0_UNREG") (class "Default")
      (node (ref "R15") (pin "2") (pinfunction "2_2") (pintype "passive"))
    )
    (net (code "11") (name "/5V0_UNREG_PG") (class "Default")
      (node (ref "U15") (pin "9") (pinfunction "A8_9") (pintype "input"))
    )
    (net (code "12") (name "/8V0_RX1") (class "Default")
      (node (ref "R24") (pin "2") (pinfunction "2_2") (pintype "passive"))
    )
    (net (code "13") (name "/8V0_RX2") (class "Default")
      (node (ref "R26") (pin "2") (pinfunction "2_2") (pintype "passive"))
    )
    (net (code "14") (name "/AFSK1_DET") (class "Default")
      (node (ref "U7") (pin "6") (pinfunction "A5_6") (pintype "input"))
    )
    (net (code "15") (name "/AFSK1_M0") (class "Default")
      (node (ref "U7") (pin "3") (pinfunction "A2_3") (pintype "input"))
    )
    (net (code "16") (name "/AFSK1_M1") (class "Default")
      (node (ref "U7") (pin "4") (pinfunction "A3_4") (pintype "input"))
    )
    (net (code "17") (name "/AFSK1_RXD") (class "Default")
      (node (ref "U7") (pin "2") (pinfunction "A1_2") (pintype "input"))
    )
    (net (code "18") (name "/AFSK1_TXD") (class "Default")
      (node (ref "U7") (pin "5") (pinfunction "A4_5") (pintype "input"))
    )
    (net (code "19") (name "/AFSK2_DET") (class "Default")
      (node (ref "U14") (pin "3") (pinfunction "A2_3") (pintype "input"))
    )
    (net (code "20") (name "/AFSK2_M0") (class "Default")
      (node (ref "U7") (pin "8") (pinfunction "A7_8") (pintype "input"))
    )
    (net (code "21") (name "/AFSK2_M1") (class "Default")
      (node (ref "U7") (pin "9") (pinfunction "A8_9") (pintype "input"))
    )
    (net (code "22") (name "/AFSK2_RXD") (class "Default")
      (node (ref "U7") (pin "7") (pinfunction "A6_7") (pintype "input"))
    )
    (net (code "23") (name "/AFSK2_TXD") (class "Default")
      (node (ref "U14") (pin "2") (pinfunction "A1_2") (pintype "input"))
    )
    (net (code "24") (name "/BBONE_I2C2_SCL") (class "Default")
      (node (ref "U5") (pin "3") (pinfunction "A2_3") (pintype "input"))
    )
    (net (code "25") (name "/BBONE_I2C2_SDA") (class "Default")
      (node (ref "U5") (pin "2") (pinfunction "A1_2") (pintype "input"))
    )
    (net (code "26") (name "/BB_DEBUG_0") (class "Default")
      (node (ref "U16") (pin "2") (pinfunction "A1_2") (pintype "input"))
    )
    (net (code "27") (name "/BB_DEBUG_1") (class "Default")
      (node (ref "U16") (pin "3") (pinfunction "A2_3") (pintype "input"))
    )
    (net (code "28") (name "/BB_DEBUG_2") (class "Default")
      (node (ref "U16") (pin "4") (pinfunction "A3_4") (pintype "input"))
    )
    (net (code "29") (name "/BB_DEBUG_3") (class "Default")
      (node (ref "U16") (pin "5") (pinfunction "A4_5") (pintype "input"))
    )
    (net (code "30") (name "/BB_DEBUG_4") (class "Default")
      (node (ref "U16") (pin "6") (pinfunction "A5_6") (pintype "input"))
    )
    (net (code "31") (name "/BB_DEBUG_5") (class "Default")
      (node (ref "U16") (pin "7") (pinfunction "A6_7") (pintype "input"))
    )
    (net (code "32") (name "/BB_DEBUG_6") (class "Default")
      (node (ref "U16") (pin "8") (pinfunction "A7_8") (pintype "input"))
    )
    (net (code "33") (name "/BB_DEBUG_7") (class "Default")
      (node (ref "U16") (pin "9") (pinfunction "A8_9") (pintype "input"))
    )
    (net (code "34") (name "/BB_DEBUG_8") (class "Default")
      (node (ref "U17") (pin "2") (pinfunction "A1_2") (pintype "input"))
    )
    (net (code "35") (name "/BB_DEBUG_9") (class "Default")
      (node (ref "U17") (pin "3") (pinfunction "A2_3") (pintype "input"))
    )
    (net (code "36") (name "/BB_DEBUG_10") (class "Default")
      (node (ref "U17") (pin "4") (pinfunction "A3_4") (pintype "input"))
    )
    (net (code "37") (name "/BB_DEBUG_11") (class "Default")
      (node (ref "U17") (pin "5") (pinfunction "A4_5") (pintype "input"))
    )
    (net (code "38") (name "/BB_DEBUG_12") (class "Default")
      (node (ref "U17") (pin "6") (pinfunction "A5_6") (pintype "input"))
    )
    (net (code "39") (name "/BB_DEBUG_13") (class "Default")
      (node (ref "U17") (pin "7") (pinfunction "A6_7") (pintype "input"))
    )
    (net (code "40") (name "/BB_DEBUG_14") (class "Default")
      (node (ref "U17") (pin "8") (pinfunction "A7_8") (pintype "input"))
    )
    (net (code "41") (name "/DEBUG_0") (class "Default")
      (node (ref "U3") (pin "9") (pinfunction "A8_9") (pintype "input"))
    )
    (net (code "42") (name "/DEBUG_1") (class "Default")
      (node (ref "U3") (pin "8") (pinfunction "A7_8") (pintype "input"))
    )
    (net (code "43") (name "/DEBUG_2") (class "Default")
      (node (ref "U3") (pin "7") (pinfunction "A6_7") (pintype "input"))
    )
    (net (code "44") (name "/DEBUG_3") (class "Default")
      (node (ref "U3") (pin "6") (pinfunction "A5_6") (pintype "input"))
    )
    (net (code "45") (name "/DEBUG_4") (class "Default")
      (node (ref "U3") (pin "5") (pinfunction "A4_5") (pintype "input"))
    )
    (net (code "46") (name "/DEBUG_5") (class "Default")
      (node (ref "U3") (pin "4") (pinfunction "A3_4") (pintype "input"))
    )
    (net (code "47") (name "/DEBUG_6") (class "Default")
      (node (ref "U3") (pin "3") (pinfunction "A2_3") (pintype "input"))
    )
    (net (code "48") (name "/DEBUG_7") (class "Default")
      (node (ref "U3") (pin "2") (pinfunction "A1_2") (pintype "input"))
    )
    (net (code "49") (name "/DEBUG_8") (class "Default")
      (node (ref "U2") (pin "9") (pinfunction "A8_9") (pintype "input"))
    )
    (net (code "50") (name "/DEBUG_9") (class "Default")
      (node (ref "U2") (pin "8") (pinfunction "A7_8") (pintype "input"))
    )
    (net (code "51") (name "/DEBUG_10") (class "Default")
      (node (ref "U2") (pin "7") (pinfunction "A6_7") (pintype "input"))
    )
    (net (code "52") (name "/DEBUG_11") (class "Default")
      (node (ref "U2") (pin "6") (pinfunction "A5_6") (pintype "input"))
    )
    (net (code "53") (name "/DEBUG_12") (class "Default")
      (node (ref "U2") (pin "5") (pinfunction "A4_5") (pintype "input"))
    )
    (net (code "54") (name "/DEBUG_13") (class "Default")
      (node (ref "U2") (pin "4") (pinfunction "A3_4") (pintype "input"))
    )
    (net (code "55") (name "/DEBUG_14") (class "Default")
      (node (ref "U2") (pin "3") (pinfunction "A2_3") (pintype "input"))
    )
    (net (code "56") (name "/DEBUG_15") (class "Default")
      (node (ref "U2") (pin "2") (pinfunction "A1_2") (pintype "input"))
    )
    (net (code "57") (name "/DTMF1Q1") (class "Default")
      (node (ref "U4") (pin "2") (pinfunction "A1_2") (pintype "input"))
    )
    (net (code "58") (name "/DTMF1Q2") (class "Default")
      (node (ref "U4") (pin "3") (pinfunction "A2_3") (pintype "input"))
    )
    (net (code "59") (name "/DTMF1Q3") (class "Default")
      (node (ref "U4") (pin "4") (pinfunction "A3_4") (pintype "input"))
    )
    (net (code "60") (name "/DTMF1Q4") (class "Default")
      (node (ref "U4") (pin "5") (pinfunction "A4_5") (pintype "input"))
    )
    (net (code "61") (name "/DTMF1ST") (class "Default")
      (node (ref "U4") (pin "6") (pinfunction "A5_6") (pintype "input"))
    )
    (net (code "62") (name "/DTMF2Q1") (class "Default")
      (node (ref "U4") (pin "7") (pinfunction "A6_7") (pintype "input"))
    )
    (net (code "63") (name "/DTMF2Q2") (class "Default")
      (node (ref "U4") (pin "8") (pinfunction "A7_8") (pintype "input"))
    )
    (net (code "64") (name "/DTMF2Q3") (class "Default")
      (node (ref "U4") (pin "9") (pinfunction "A8_9") (pintype "input"))
    )
    (net (code "65") (name "/DTMF2Q4") (class "Default")
      (node (ref "U15") (pin "6") (pinfunction "A5_6") (pintype "input"))
    )
    (net (code "66") (name "/DTMF2ST") (class "Default")
      (node (ref "U15") (pin "7") (pinfunction "A6_7") (pintype "input"))
    )
    (net (code "67") (name "/I2C0_SCL") (class "Default")
      (node (ref "U5") (pin "5") (pinfunction "A4_5") (pintype "input"))
    )
    (net (code "68") (name "/I2C0_SDA") (class "Default")
      (node (ref "U5") (pin "4") (pinfunction "A3_4") (pintype "input"))
    )
    (net (code "69") (name "/I2C1_SCL") (class "Default")
      (node (ref "U5") (pin "7") (pinfunction "A6_7") (pintype "input"))
    )
    (net (code "70") (name "/I2C1_SDA") (class "Default")
      (node (ref "U5") (pin "6") (pinfunction "A5_6") (pintype "input"))
    )
    (net (code "71") (name "/I2C2_SCL") (class "Default")
      (node (ref "U5") (pin "9") (pinfunction "A8_9") (pintype "input"))
    )
    (net (code "72") (name "/I2C2_SDA") (class "Default")
      (node (ref "U5") (pin "8") (pinfunction "A7_8") (pintype "input"))
    )
    (net (code "73") (name "/RXDATA1") (class "Default")
      (node (ref "U14") (pin "5") (pinfunction "A4_5") (pintype "input"))
    )
    (net (code "74") (name "/RXDATA2") (class "Default")
      (node (ref "U15") (pin "2") (pinfunction "A1_2") (pintype "input"))
    )
    (net (code "75") (name "/RXHOLD1") (class "Default")
      (node (ref "U14") (pin "8") (pinfunction "A7_8") (pintype "input"))
    )
    (net (code "76") (name "/RXHOLD2") (class "Default")
      (node (ref "U15") (pin "5") (pinfunction "A4_5") (pintype "input"))
    )
    (net (code "77") (name "/RX_S{slash}N1") (class "Default")
      (node (ref "U14") (pin "7") (pinfunction "A6_7") (pintype "input"))
    )
    (net (code "78") (name "/RX_S{slash}N2") (class "Default")
      (node (ref "U15") (pin "4") (pinfunction "A3_4") (pintype "input"))
    )
    (net (code "79") (name "/S0") (class "Default")
      (node (ref "U6") (pin "2") (pinfunction "A1_2") (pintype "input"))
    )
    (net (code "80") (name "/S1") (class "Default")
      (node (ref "U6") (pin "3") (pinfunction "A2_3") (pintype "input"))
    )
    (net (code "81") (name "/S2") (class "Default")
      (node (ref "U6") (pin "4") (pinfunction "A3_4") (pintype "input"))
    )
    (net (code "82") (name "/S3") (class "Default")
      (node (ref "U6") (pin "5") (pinfunction "A4_5") (pintype "input"))
    )
    (net (code "83") (name "/S4") (class "Default")
      (node (ref "U6") (pin "6") (pinfunction "A5_6") (pintype "input"))
    )
    (net (code "84") (name "/S5") (class "Default")
      (node (ref "U6") (pin "7") (pinfunction "A6_7") (pintype "input"))
    )
    (net (code "85") (name "/S6") (class "Default")
      (node (ref "U6") (pin "8") (pinfunction "A7_8") (pintype "input"))
    )
    (net (code "86") (name "/S7") (class "Default")
      (node (ref "U6") (pin "9") (pinfunction "A8_9") (pintype "input"))
    )
    (net (code "87") (name "/TXDATA1") (class "Default")
      (node (ref "U14") (pin "4") (pinfunction "A3_4") (pintype "input"))
    )
    (net (code "88") (name "/TXDATA2") (class "Default")
      (node (ref "U14") (pin "9") (pinfunction "A8_9") (pintype "input"))
    )
    (net (code "89") (name "/TXEN1") (class "Default")
      (node (ref "U14") (pin "6") (pinfunction "A5_6") (pintype "input"))
    )
    (net (code "90") (name "/TXEN2") (class "Default")
      (node (ref "U15") (pin "3") (pinfunction "A2_3") (pintype "input"))
    )
    (net (code "91") (name "/VVAR_TX1") (class "Default")
      (node (ref "R25") (pin "2") (pinfunction "2_2") (pintype "passive"))
    )
    (net (code "92") (name "/VVAR_TX2") (class "Default")
      (node (ref "R27") (pin "2") (pinfunction "2_2") (pintype "passive"))
    )
    (net (code "93") (name "/V_BATT") (class "Default")
      (node (ref "R12") (pin "2") (pinfunction "2_2") (pintype "passive"))
    )
    (net (code "94") (name "/V_LOAD") (class "Default")
      (node (ref "R13") (pin "2") (pinfunction "2_2") (pintype "passive"))
    )
    (net (code "95") (name "3V3_UNREG") (class "Default")
      (node (ref "C10") (pin "2") (pinfunction "2_2") (pintype "passive"))
      (node (ref "C11") (pin "2") (pinfunction "2_2") (pintype "passive"))
      (node (ref "C12") (pin "2") (pinfunction "2_2") (pintype "passive"))
      (node (ref "C13") (pin "2") (pinfunction "2_2") (pintype "passive"))
      (node (ref "C2") (pin "2") (pinfunction "2_2") (pintype "passive"))
      (node (ref "C3") (pin "2") (pinfunction "2_2") (pintype "passive"))
      (node (ref "C4") (pin "2") (pinfunction "2_2") (pintype "passive"))
      (node (ref "C5") (pin "2") (pinfunction "2_2") (pintype "passive"))
      (node (ref "C6") (pin "2") (pinfunction "2_2") (pintype "passive"))
      (node (ref "C7") (pin "2") (pinfunction "2_2") (pintype "passive"))
      (node (ref "C8") (pin "2") (pinfunction "2_2") (pintype "passive"))
      (node (ref "C9") (pin "2") (pinfunction "2_2") (pintype "passive"))
      (node (ref "LED10") (pin "3") (pinfunction "VCC_3") (pintype "passive"))
      (node (ref "LED101") (pin "3") (pinfunction "VCC_3") (pintype "passive"))
      (node (ref "LED102") (pin "3") (pinfunction "VCC_3") (pintype "passive"))
      (node (ref "LED103") (pin "3") (pinfunction "VCC_3") (pintype "passive"))
      (node (ref "LED104") (pin "3") (pinfunction "VCC_3") (pintype "passive"))
      (node (ref "LED105") (pin "3") (pinfunction "VCC_3") (pintype "passive"))
      (node (ref "LED106") (pin "3") (pinfunction "VCC_3") (pintype "passive"))
      (node (ref "LED107") (pin "3") (pinfunction "VCC_3") (pintype "passive"))
      (node (ref "LED108") (pin "3") (pinfunction "VCC_3") (pintype "passive"))
      (node (ref "LED109") (pin "3") (pinfunction "VCC_3") (pintype "passive"))
      (node (ref "LED11") (pin "3") (pinfunction "VCC_3") (pintype "passive"))
      (node (ref "LED111") (pin "3") (pinfunction "VCC_3") (pintype "passive"))
      (node (ref "LED112") (pin "3") (pinfunction "VCC_3") (pintype "passive"))
      (node (ref "LED12") (pin "3") (pinfunction "VCC_3") (pintype "passive"))
      (node (ref "LED13") (pin "3") (pinfunction "VCC_3") (pintype "passive"))
      (node (ref "LED14") (pin "3") (pinfunction "VCC_3") (pintype "passive"))
      (node (ref "LED15") (pin "3") (pinfunction "VCC_3") (pintype "passive"))
      (node (ref "LED16") (pin "3") (pinfunction "VCC_3") (pintype "passive"))
      (node (ref "LED17") (pin "3") (pinfunction "VCC_3") (pintype "passive"))
      (node (ref "LED19") (pin "3") (pinfunction "VCC_3") (pintype "passive"))
      (node (ref "LED20") (pin "3") (pinfunction "VCC_3") (pintype "passive"))
      (node (ref "LED21") (pin "3") (pinfunction "VCC_3") (pintype "passive"))
      (node (ref "LED22") (pin "3") (pinfunction "VCC_3") (pintype "passive"))
      (node (ref "LED23") (pin "3") (pinfunction "VCC_3") (pintype "passive"))
      (node (ref "LED24") (pin "3") (pinfunction "VCC_3") (pintype "passive"))
      (node (ref "LED25") (pin "3") (pinfunction "VCC_3") (pintype "passive"))
      (node (ref "LED26") (pin "3") (pinfunction "VCC_3") (pintype "passive"))
      (node (ref "LED27") (pin "3") (pinfunction "VCC_3") (pintype "passive"))
      (node (ref "LED28") (pin "3") (pinfunction "VCC_3") (pintype "passive"))
      (node (ref "LED29") (pin "3") (pinfunction "VCC_3") (pintype "passive"))
      (node (ref "LED30") (pin "3") (pinfunction "VCC_3") (pintype "passive"))
      (node (ref "LED31") (pin "3") (pinfunction "VCC_3") (pintype "passive"))
      (node (ref "LED32") (pin "3") (pinfunction "VCC_3") (pintype "passive"))
      (node (ref "LED33") (pin "3") (pinfunction "VCC_3") (pintype "passive"))
      (node (ref "LED34") (pin "3") (pinfunction "VCC_3") (pintype "passive"))
      (node (ref "LED35") (pin "3") (pinfunction "VCC_3") (pintype "passive"))
      (node (ref "LED36") (pin "3") (pinfunction "VCC_3") (pintype "passive"))
      (node (ref "LED38") (pin "3") (pinfunction "VCC_3") (pintype "passive"))
      (node (ref "LED39") (pin "3") (pinfunction "VCC_3") (pintype "passive"))
      (node (ref "LED40") (pin "3") (pinfunction "VCC_3") (pintype "passive"))
      (node (ref "LED41") (pin "3") (pinfunction "VCC_3") (pintype "passive"))
      (node (ref "LED42") (pin "3") (pinfunction "VCC_3") (pintype "passive"))
      (node (ref "LED43") (pin "3") (pinfunction "VCC_3") (pintype "passive"))
      (node (ref "LED44") (pin "3") (pinfunction "VCC_3") (pintype "passive"))
      (node (ref "LED45") (pin "3") (pinfunction "VCC_3") (pintype "passive"))
      (node (ref "LED46") (pin "3") (pinfunction "VCC_3") (pintype "passive"))
      (node (ref "LED47") (pin "3") (pinfunction "VCC_3") (pintype "passive"))
      (node (ref "LED48") (pin "3") (pinfunction "VCC_3") (pintype "passive"))
      (node (ref "LED49") (pin "3") (pinfunction "VCC_3") (pintype "passive"))
      (node (ref "LED50") (pin "3") (pinfunction "VCC_3") (pintype "passive"))
      (node (ref "LED51") (pin "3") (pinfunction "VCC_3") (pintype "passive"))
      (node (ref "LED52") (pin "3") (pinfunction "VCC_3") (pintype "passive"))
      (node (ref "LED53") (pin "3") (pinfunction "VCC_3") (pintype "passive"))
      (node (ref "LED54") (pin "3") (pinfunction "VCC_3") (pintype "passive"))
      (node (ref "LED55") (pin "3") (pinfunction "VCC_3") (pintype "passive"))
      (node (ref "LED6") (pin "3") (pinfunction "VCC_3") (pintype "passive"))
      (node (ref "LED63") (pin "3") (pinfunction "VCC_3") (pintype "passive"))
      (node (ref "LED64") (pin "3") (pinfunction "VCC_3") (pintype "passive"))
      (node (ref "LED65") (pin "3") (pinfunction "VCC_3") (pintype "passive"))
      (node (ref "LED66") (pin "3") (pinfunction "VCC_3") (pintype "passive"))
      (node (ref "LED67") (pin "3") (pinfunction "VCC_3") (pintype "passive"))
      (node (ref "LED68") (pin "3") (pinfunction "VCC_3") (pintype "passive"))
      (node (ref "LED69") (pin "3") (pinfunction "VCC_3") (pintype "passive"))
      (node (ref "LED7") (pin "3") (pinfunction "VCC_3") (pintype "passive"))
      (node (ref "LED70") (pin "3") (pinfunction "VCC_3") (pintype "passive"))
      (node (ref "LED71") (pin "3") (pinfunction "VCC_3") (pintype "passive"))
      (node (ref "LED72") (pin "3") (pinfunction "VCC_3") (pintype "passive"))
      (node (ref "LED73") (pin "3") (pinfunction "VCC_3") (pintype "passive"))
      (node (ref "LED74") (pin "3") (pinfunction "VCC_3") (pintype "passive"))
      (node (ref "LED75") (pin "3") (pinfunction "VCC_3") (pintype "passive"))
      (node (ref "LED76") (pin "3") (pinfunction "VCC_3") (pintype "passive"))
      (node (ref "LED77") (pin "3") (pinfunction "VCC_3") (pintype "passive"))
      (node (ref "LED78") (pin "3") (pinfunction "VCC_3") (pintype "passive"))
      (node (ref "LED79") (pin "3") (pinfunction "VCC_3") (pintype "passive"))
      (node (ref "LED8") (pin "3") (pinfunction "VCC_3") (pintype "passive"))
      (node (ref "LED80") (pin "3") (pinfunction "VCC_3") (pintype "passive"))
      (node (ref "LED82") (pin "3") (pinfunction "VCC_3") (pintype "passive"))
      (node (ref "LED83") (pin "3") (pinfunction "VCC_3") (pintype "passive"))
      (node (ref "LED84") (pin "3") (pinfunction "VCC_3") (pintype "passive"))
      (node (ref "LED85") (pin "3") (pinfunction "VCC_3") (pintype "passive"))
      (node (ref "LED86") (pin "3") (pinfunction "VCC_3") (pintype "passive"))
      (node (ref "LED87") (pin "3") (pinfunction "VCC_3") (pintype "passive"))
      (node (ref "LED88") (pin "3") (pinfunction "VCC_3") (pintype "passive"))
      (node (ref "LED89") (pin "3") (pinfunction "VCC_3") (pintype "passive"))
      (node (ref "LED9") (pin "3") (pinfunction "VCC_3") (pintype "passive"))
      (node (ref "LED90") (pin "3") (pinfunction "VCC_3") (pintype "passive"))
      (node (ref "LED91") (pin "3") (pinfunction "VCC_3") (pintype "passive"))
      (node (ref "LED92") (pin "3") (pinfunction "VCC_3") (pintype "passive"))
      (node (ref "LED93") (pin "3") (pinfunction "VCC_3") (pintype "passive"))
      (node (ref "LED94") (pin "3") (pinfunction "VCC_3") (pintype "passive"))
      (node (ref "LED95") (pin "3") (pinfunction "VCC_3") (pintype "passive"))
      (node (ref "LED96") (pin "3") (pinfunction "VCC_3") (pintype "passive"))
      (node (ref "LED97") (pin "3") (pinfunction "VCC_3") (pintype "passive"))
      (node (ref "LED98") (pin "3") (pinfunction "VCC_3") (pintype "passive"))
      (node (ref "LED99") (pin "3") (pinfunction "VCC_3") (pintype "passive"))
      (node (ref "R14") (pin "2") (pinfunction "2_2") (pintype "passive"))
      (node (ref "U14") (pin "20") (pinfunction "VDD_20") (pintype "power_in"))
      (node (ref "U15") (pin "20") (pinfunction "VDD_20") (pintype "power_in"))
      (node (ref "U16") (pin "20") (pinfunction "VDD_20") (pintype "power_in"))
      (node (ref "U17") (pin "20") (pinfunction "VDD_20") (pintype "power_in"))
      (node (ref "U18") (pin "20") (pinfunction "VDD_20") (pintype "power_in"))
      (node (ref "U19") (pin "20") (pinfunction "VDD_20") (pintype "power_in"))
      (node (ref "U2") (pin "20") (pinfunction "VDD_20") (pintype "power_in"))
      (node (ref "U3") (pin "20") (pinfunction "VDD_20") (pintype "power_in"))
      (node (ref "U4") (pin "20") (pinfunction "VDD_20") (pintype "power_in"))
      (node (ref "U5") (pin "20") (pinfunction "VDD_20") (pintype "power_in"))
      (node (ref "U6") (pin "20") (pinfunction "VDD_20") (pintype "power_in"))
      (node (ref "U7") (pin "20") (pinfunction "VDD_20") (pintype "power_in"))
    )
    (net (code "96") (name "GND") (class "Default")
      (node (ref "C10") (pin "1") (pinfunction "1_1") (pintype "passive"))
      (node (ref "C11") (pin "1") (pinfunction "1_1") (pintype "passive"))
      (node (ref "C12") (pin "1") (pinfunction "1_1") (pintype "passive"))
      (node (ref "C13") (pin "1") (pinfunction "1_1") (pintype "passive"))
      (node (ref "C2") (pin "1") (pinfunction "1_1") (pintype "passive"))
      (node (ref "C3") (pin "1") (pinfunction "1_1") (pintype "passive"))
      (node (ref "C4") (pin "1") (pinfunction "1_1") (pintype "passive"))
      (node (ref "C5") (pin "1") (pinfunction "1_1") (pintype "passive"))
      (node (ref "C6") (pin "1") (pinfunction "1_1") (pintype "passive"))
      (node (ref "C7") (pin "1") (pinfunction "1_1") (pintype "passive"))
      (node (ref "C8") (pin "1") (pinfunction "1_1") (pintype "passive"))
      (node (ref "C9") (pin "1") (pinfunction "1_1") (pintype "passive"))
      (node (ref "LED1") (pin "2") (pinfunction "K_2") (pintype "passive"))
      (node (ref "LED10") (pin "1") (pinfunction "GND_1") (pintype "passive"))
      (node (ref "LED100") (pin "2") (pinfunction "K_2") (pintype "passive"))
      (node (ref "LED101") (pin "1") (pinfunction "GND_1") (pintype "passive"))
      (node (ref "LED102") (pin "1") (pinfunction "GND_1") (pintype "passive"))
      (node (ref "LED103") (pin "1") (pinfunction "GND_1") (pintype "passive"))
      (node (ref "LED104") (pin "1") (pinfunction "GND_1") (pintype "passive"))
      (node (ref "LED105") (pin "1") (pinfunction "GND_1") (pintype "passive"))
      (node (ref "LED106") (pin "1") (pinfunction "GND_1") (pintype "passive"))
      (node (ref "LED107") (pin "1") (pinfunction "GND_1") (pintype "passive"))
      (node (ref "LED108") (pin "1") (pinfunction "GND_1") (pintype "passive"))
      (node (ref "LED109") (pin "1") (pinfunction "GND_1") (pintype "passive"))
      (node (ref "LED11") (pin "1") (pinfunction "GND_1") (pintype "passive"))
      (node (ref "LED111") (pin "1") (pinfunction "GND_1") (pintype "passive"))
      (node (ref "LED112") (pin "1") (pinfunction "GND_1") (pintype "passive"))
      (node (ref "LED12") (pin "1") (pinfunction "GND_1") (pintype "passive"))
      (node (ref "LED13") (pin "1") (pinfunction "GND_1") (pintype "passive"))
      (node (ref "LED14") (pin "1") (pinfunction "GND_1") (pintype "passive"))
      (node (ref "LED15") (pin "1") (pinfunction "GND_1") (pintype "passive"))
      (node (ref "LED16") (pin "1") (pinfunction "GND_1") (pintype "passive"))
      (node (ref "LED17") (pin "1") (pinfunction "GND_1") (pintype "passive"))
      (node (ref "LED18") (pin "2") (pinfunction "K_2") (pintype "passive"))
      (node (ref "LED19") (pin "1") (pinfunction "GND_1") (pintype "passive"))
      (node (ref "LED2") (pin "2") (pinfunction "K_2") (pintype "passive"))
      (node (ref "LED20") (pin "1") (pinfunction "GND_1") (pintype "passive"))
      (node (ref "LED21") (pin "1") (pinfunction "GND_1") (pintype "passive"))
      (node (ref "LED22") (pin "1") (pinfunction "GND_1") (pintype "passive"))
      (node (ref "LED23") (pin "1") (pinfunction "GND_1") (pintype "passive"))
      (node (ref "LED24") (pin "1") (pinfunction "GND_1") (pintype "passive"))
      (node (ref "LED25") (pin "1") (pinfunction "GND_1") (pintype "passive"))
      (node (ref "LED26") (pin "1") (pinfunction "GND_1") (pintype "passive"))
      (node (ref "LED27") (pin "1") (pinfunction "GND_1") (pintype "passive"))
      (node (ref "LED28") (pin "1") (pinfunction "GND_1") (pintype "passive"))
      (node (ref "LED29") (pin "1") (pinfunction "GND_1") (pintype "passive"))
      (node (ref "LED3") (pin "2") (pinfunction "K_2") (pintype "passive"))
      (node (ref "LED30") (pin "1") (pinfunction "GND_1") (pintype "passive"))
      (node (ref "LED31") (pin "1") (pinfunction "GND_1") (pintype "passive"))
      (node (ref "LED32") (pin "1") (pinfunction "GND_1") (pintype "passive"))
      (node (ref "LED33") (pin "1") (pinfunction "GND_1") (pintype "passive"))
      (node (ref "LED34") (pin "1") (pinfunction "GND_1") (pintype "passive"))
      (node (ref "LED35") (pin "1") (pinfunction "GND_1") (pintype "passive"))
      (node (ref "LED36") (pin "1") (pinfunction "GND_1") (pintype "passive"))
      (node (ref "LED37") (pin "2") (pinfunction "K_2") (pintype "passive"))
      (node (ref "LED38") (pin "1") (pinfunction "GND_1") (pintype "passive"))
      (node (ref "LED39") (pin "1") (pinfunction "GND_1") (pintype "passive"))
      (node (ref "LED4") (pin "2") (pinfunction "K_2") (pintype "passive"))
      (node (ref "LED40") (pin "1") (pinfunction "GND_1") (pintype "passive"))
      (node (ref "LED41") (pin "1") (pinfunction "GND_1") (pintype "passive"))
      (node (ref "LED42") (pin "1") (pinfunction "GND_1") (pintype "passive"))
      (node (ref "LED43") (pin "1") (pinfunction "GND_1") (pintype "passive"))
      (node (ref "LED44") (pin "1") (pinfunction "GND_1") (pintype "passive"))
      (node (ref "LED45") (pin "1") (pinfunction "GND_1") (pintype "passive"))
      (node (ref "LED46") (pin "1") (pinfunction "GND_1") (pintype "passive"))
      (node (ref "LED47") (pin "1") (pinfunction "GND_1") (pintype "passive"))
      (node (ref "LED48") (pin "1") (pinfunction "GND_1") (pintype "passive"))
      (node (ref "LED49") (pin "1") (pinfunction "GND_1") (pintype "passive"))
      (node (ref "LED5") (pin "2") (pinfunction "K_2") (pintype "passive"))
      (node (ref "LED50") (pin "1") (pinfunction "GND_1") (pintype "passive"))
      (node (ref "LED51") (pin "1") (pinfunction "GND_1") (pintype "passive"))
      (node (ref "LED52") (pin "1") (pinfunction "GND_1") (pintype "passive"))
      (node (ref "LED53") (pin "1") (pinfunction "GND_1") (pintype "passive"))
      (node (ref "LED54") (pin "1") (pinfunction "GND_1") (pintype "passive"))
      (node (ref "LED55") (pin "1") (pinfunction "GND_1") (pintype "passive"))
      (node (ref "LED56") (pin "2") (pinfunction "K_2") (pintype "passive"))
      (node (ref "LED57") (pin "2") (pinfunction "K_2") (pintype "passive"))
      (node (ref "LED58") (pin "2") (pinfunction "K_2") (pintype "passive"))
      (node (ref "LED59") (pin "2") (pinfunction "K_2") (pintype "passive"))
      (node (ref "LED6") (pin "1") (pinfunction "GND_1") (pintype "passive"))
      (node (ref "LED60") (pin "2") (pinfunction "K_2") (pintype "passive"))
      (node (ref "LED61") (pin "2") (pinfunction "K_2") (pintype "passive"))
      (node (ref "LED62") (pin "2") (pinfunction "K_2") (pintype "passive"))
      (node (ref "LED63") (pin "1") (pinfunction "GND_1") (pintype "passive"))
      (node (ref "LED64") (pin "1") (pinfunction "GND_1") (pintype "passive"))
      (node (ref "LED65") (pin "1") (pinfunction "GND_1") (pintype "passive"))
      (node (ref "LED66") (pin "1") (pinfunction "GND_1") (pintype "passive"))
      (node (ref "LED67") (pin "1") (pinfunction "GND_1") (pintype "passive"))
      (node (ref "LED68") (pin "1") (pinfunction "GND_1") (pintype "passive"))
      (node (ref "LED69") (pin "1") (pinfunction "GND_1") (pintype "passive"))
      (node (ref "LED7") (pin "1") (pinfunction "GND_1") (pintype "passive"))
      (node (ref "LED70") (pin "1") (pinfunction "GND_1") (pintype "passive"))
      (node (ref "LED71") (pin "1") (pinfunction "GND_1") (pintype "passive"))
      (node (ref "LED72") (pin "1") (pinfunction "GND_1") (pintype "passive"))
      (node (ref "LED73") (pin "1") (pinfunction "GND_1") (pintype "passive"))
      (node (ref "LED74") (pin "1") (pinfunction "GND_1") (pintype "passive"))
      (node (ref "LED75") (pin "1") (pinfunction "GND_1") (pintype "passive"))
      (node (ref "LED76") (pin "1") (pinfunction "GND_1") (pintype "passive"))
      (node (ref "LED77") (pin "1") (pinfunction "GND_1") (pintype "passive"))
      (node (ref "LED78") (pin "1") (pinfunction "GND_1") (pintype "passive"))
      (node (ref "LED79") (pin "1") (pinfunction "GND_1") (pintype "passive"))
      (node (ref "LED8") (pin "1") (pinfunction "GND_1") (pintype "passive"))
      (node (ref "LED80") (pin "1") (pinfunction "GND_1") (pintype "passive"))
      (node (ref "LED81") (pin "2") (pinfunction "K_2") (pintype "passive"))
      (node (ref "LED82") (pin "1") (pinfunction "GND_1") (pintype "passive"))
      (node (ref "LED83") (pin "1") (pinfunction "GND_1") (pintype "passive"))
      (node (ref "LED84") (pin "1") (pinfunction "GND_1") (pintype "passive"))
      (node (ref "LED85") (pin "1") (pinfunction "GND_1") (pintype "passive"))
      (node (ref "LED86") (pin "1") (pinfunction "GND_1") (pintype "passive"))
      (node (ref "LED87") (pin "1") (pinfunction "GND_1") (pintype "passive"))
      (node (ref "LED88") (pin "1") (pinfunction "GND_1") (pintype "passive"))
      (node (ref "LED89") (pin "1") (pinfunction "GND_1") (pintype "passive"))
      (node (ref "LED9") (pin "1") (pinfunction "GND_1") (pintype "passive"))
      (node (ref "LED90") (pin "1") (pinfunction "GND_1") (pintype "passive"))
      (node (ref "LED91") (pin "1") (pinfunction "GND_1") (pintype "passive"))
      (node (ref "LED92") (pin "1") (pinfunction "GND_1") (pintype "passive"))
      (node (ref "LED93") (pin "1") (pinfunction "GND_1") (pintype "passive"))
      (node (ref "LED94") (pin "1") (pinfunction "GND_1") (pintype "passive"))
      (node (ref "LED95") (pin "1") (pinfunction "GND_1") (pintype "passive"))
      (node (ref "LED96") (pin "1") (pinfunction "GND_1") (pintype "passive"))
      (node (ref "LED97") (pin "1") (pinfunction "GND_1") (pintype "passive"))
      (node (ref "LED98") (pin "1") (pinfunction "GND_1") (pintype "passive"))
      (node (ref "LED99") (pin "1") (pinfunction "GND_1") (pintype "passive"))
      (node (ref "U14") (pin "1") (pinfunction "~{OE}1_1") (pintype "input"))
      (node (ref "U14") (pin "10") (pinfunction "GND_10") (pintype "power_in"))
      (node (ref "U14") (pin "19") (pinfunction "~{OE}2_19") (pintype "input"))
      (node (ref "U15") (pin "1") (pinfunction "~{OE}1_1") (pintype "input"))
      (node (ref "U15") (pin "10") (pinfunction "GND_10") (pintype "power_in"))
      (node (ref "U15") (pin "19") (pinfunction "~{OE}2_19") (pintype "input"))
      (node (ref "U16") (pin "1") (pinfunction "~{OE}1_1") (pintype "input"))
      (node (ref "U16") (pin "10") (pinfunction "GND_10") (pintype "power_in"))
      (node (ref "U16") (pin "19") (pinfunction "~{OE}2_19") (pintype "input"))
      (node (ref "U17") (pin "1") (pinfunction "~{OE}1_1") (pintype "input"))
      (node (ref "U17") (pin "10") (pinfunction "GND_10") (pintype "power_in"))
      (node (ref "U17") (pin "19") (pinfunction "~{OE}2_19") (pintype "input"))
      (node (ref "U18") (pin "1") (pinfunction "~{OE}1_1") (pintype "input"))
      (node (ref "U18") (pin "10") (pinfunction "GND_10") (pintype "power_in"))
      (node (ref "U18") (pin "19") (pinfunction "~{OE}2_19") (pintype "input"))
      (node (ref "U19") (pin "1") (pinfunction "~{OE}1_1") (pintype "input"))
      (node (ref "U19") (pin "19") (pinfunction "~{OE}2_19") (pintype "input"))
      (node (ref "U2") (pin "1") (pinfunction "~{OE}1_1") (pintype "input"))
      (node (ref "U2") (pin "10") (pinfunction "GND_10") (pintype "power_in"))
      (node (ref "U2") (pin "19") (pinfunction "~{OE}2_19") (pintype "input"))
      (node (ref "U3") (pin "1") (pinfunction "~{OE}1_1") (pintype "input"))
      (node (ref "U3") (pin "10") (pinfunction "GND_10") (pintype "power_in"))
      (node (ref "U3") (pin "19") (pinfunction "~{OE}2_19") (pintype "input"))
      (node (ref "U4") (pin "1") (pinfunction "~{OE}1_1") (pintype "input"))
      (node (ref "U4") (pin "10") (pinfunction "GND_10") (pintype "power_in"))
      (node (ref "U4") (pin "19") (pinfunction "~{OE}2_19") (pintype "input"))
      (node (ref "U5") (pin "1") (pinfunction "~{OE}1_1") (pintype "input"))
      (node (ref "U5") (pin "10") (pinfunction "GND_10") (pintype "power_in"))
      (node (ref "U5") (pin "19") (pinfunction "~{OE}2_19") (pintype "input"))
      (node (ref "U6") (pin "1") (pinfunction "~{OE}1_1") (pintype "input"))
      (node (ref "U6") (pin "10") (pinfunction "GND_10") (pintype "power_in"))
      (node (ref "U6") (pin "19") (pinfunction "~{OE}2_19") (pintype "input"))
      (node (ref "U7") (pin "1") (pinfunction "~{OE}1_1") (pintype "input"))
      (node (ref "U7") (pin "10") (pinfunction "GND_10") (pintype "power_in"))
      (node (ref "U7") (pin "19") (pinfunction "~{OE}2_19") (pintype "input"))
    )
    (net (code "97") (name "Net-(LED1-A)") (class "Default")
      (node (ref "LED1") (pin "1") (pinfunction "A_1") (pintype "passive"))
      (node (ref "R12") (pin "1") (pinfunction "1_1") (pintype "passive"))
    )
    (net (code "98") (name "Net-(LED2-A)") (class "Default")
      (node (ref "LED2") (pin "1") (pinfunction "A_1") (pintype "passive"))
      (node (ref "R13") (pin "1") (pinfunction "1_1") (pintype "passive"))
    )
    (net (code "99") (name "Net-(LED3-A)") (class "Default")
      (node (ref "LED3") (pin "1") (pinfunction "A_1") (pintype "passive"))
      (node (ref "R14") (pin "1") (pinfunction "1_1") (pintype "passive"))
    )
    (net (code "100") (name "Net-(LED4-A)") (class "Default")
      (node (ref "LED4") (pin "1") (pinfunction "A_1") (pintype "passive"))
      (node (ref "R15") (pin "1") (pinfunction "1_1") (pintype "passive"))
    )
    (net (code "101") (name "Net-(LED5-A)") (class "Default")
      (node (ref "LED5") (pin "1") (pinfunction "A_1") (pintype "passive"))
      (node (ref "R16") (pin "1") (pinfunction "1_1") (pintype "passive"))
    )
    (net (code "102") (name "Net-(LED6-RES)") (class "Default")
      (node (ref "LED6") (pin "2") (pinfunction "RES_2") (pintype "passive"))
      (node (ref "U8") (pin "16") (pinfunction "1B_16") (pintype "passive"))
    )
    (net (code "103") (name "Net-(LED7-RES)") (class "Default")
      (node (ref "LED7") (pin "2") (pinfunction "RES_2") (pintype "passive"))
      (node (ref "U9") (pin "16") (pinfunction "1B_16") (pintype "passive"))
    )
    (net (code "104") (name "Net-(LED8-RES)") (class "Default")
      (node (ref "LED8") (pin "2") (pinfunction "RES_2") (pintype "passive"))
      (node (ref "U10") (pin "16") (pinfunction "1B_16") (pintype "passive"))
    )
    (net (code "105") (name "Net-(LED9-RES)") (class "Default")
      (node (ref "LED9") (pin "2") (pinfunction "RES_2") (pintype "passive"))
      (node (ref "U21") (pin "12") (pinfunction "5B_12") (pintype "passive"))
    )
    (net (code "106") (name "Net-(LED10-RES)") (class "Default")
      (node (ref "LED10") (pin "2") (pinfunction "RES_2") (pintype "passive"))
      (node (ref "U12") (pin "16") (pinfunction "1B_16") (pintype "passive"))
    )
    (net (code "107") (name "Net-(LED11-RES)") (class "Default")
      (node (ref "LED11") (pin "2") (pinfunction "RES_2") (pintype "passive"))
      (node (ref "U13") (pin "16") (pinfunction "1B_16") (pintype "passive"))
    )
    (net (code "108") (name "Net-(LED12-RES)") (class "Default")
      (node (ref "LED12") (pin "2") (pinfunction "RES_2") (pintype "passive"))
      (node (ref "U8") (pin "15") (pinfunction "2B_15") (pintype "passive"))
    )
    (net (code "109") (name "Net-(LED13-RES)") (class "Default")
      (node (ref "LED13") (pin "2") (pinfunction "RES_2") (pintype "passive"))
      (node (ref "U9") (pin "15") (pinfunction "2B_15") (pintype "passive"))
    )
    (net (code "110") (name "Net-(LED14-RES)") (class "Default")
      (node (ref "LED14") (pin "2") (pinfunction "RES_2") (pintype "passive"))
      (node (ref "U10") (pin "15") (pinfunction "2B_15") (pintype "passive"))
    )
    (net (code "111") (name "Net-(LED15-RES)") (class "Default")
      (node (ref "LED15") (pin "2") (pinfunction "RES_2") (pintype "passive"))
      (node (ref "U21") (pin "11") (pinfunction "6B_11") (pintype "passive"))
    )
    (net (code "112") (name "Net-(LED16-RES)") (class "Default")
      (node (ref "LED16") (pin "2") (pinfunction "RES_2") (pintype "passive"))
      (node (ref "U12") (pin "15") (pinfunction "2B_15") (pintype "passive"))
    )
    (net (code "113") (name "Net-(LED17-RES)") (class "Default")
      (node (ref "LED17") (pin "2") (pinfunction "RES_2") (pintype "passive"))
      (node (ref "U13") (pin "15") (pinfunction "2B_15") (pintype "passive"))
    )
    (net (code "114") (name "Net-(LED18-A)") (class "Default")
      (node (ref "LED18") (pin "1") (pinfunction "A_1") (pintype "passive"))
      (node (ref "R17") (pin "1") (pinfunction "1_1") (pintype "passive"))
    )
    (net (code "115") (name "Net-(LED19-RES)") (class "Default")
      (node (ref "LED19") (pin "2") (pinfunction "RES_2") (pintype "passive"))
      (node (ref "U8") (pin "14") (pinfunction "3B_14") (pintype "passive"))
    )
    (net (code "116") (name "Net-(LED20-RES)") (class "Default")
      (node (ref "LED20") (pin "2") (pinfunction "RES_2") (pintype "passive"))
      (node (ref "U9") (pin "14") (pinfunction "3B_14") (pintype "passive"))
    )
    (net (code "117") (name "Net-(LED21-RES)") (class "Default")
      (node (ref "LED21") (pin "2") (pinfunction "RES_2") (pintype "passive"))
      (node (ref "U10") (pin "14") (pinfunction "3B_14") (pintype "passive"))
    )
    (net (code "118") (name "Net-(LED22-RES)") (class "Default")
      (node (ref "LED22") (pin "2") (pinfunction "RES_2") (pintype "passive"))
      (node (ref "U11") (pin "14") (pinfunction "3B_14") (pintype "passive"))
    )
    (net (code "119") (name "Net-(LED23-RES)") (class "Default")
      (node (ref "LED23") (pin "2") (pinfunction "RES_2") (pintype "passive"))
      (node (ref "U12") (pin "14") (pinfunction "3B_14") (pintype "passive"))
    )
    (net (code "120") (name "Net-(LED24-RES)") (class "Default")
      (node (ref "LED24") (pin "2") (pinfunction "RES_2") (pintype "passive"))
      (node (ref "U13") (pin "14") (pinfunction "3B_14") (pintype "passive"))
    )
    (net (code "121") (name "Net-(LED25-RES)") (class "Default")
      (node (ref "LED25") (pin "2") (pinfunction "RES_2") (pintype "passive"))
      (node (ref "U8") (pin "13") (pinfunction "4B_13") (pintype "passive"))
    )
    (net (code "122") (name "Net-(LED26-RES)") (class "Default")
      (node (ref "LED26") (pin "2") (pinfunction "RES_2") (pintype "passive"))
      (node (ref "U9") (pin "13") (pinfunction "4B_13") (pintype "passive"))
    )
    (net (code "123") (name "Net-(LED27-RES)") (class "Default")
      (node (ref "LED27") (pin "2") (pinfunction "RES_2") (pintype "passive"))
      (node (ref "U10") (pin "13") (pinfunction "4B_13") (pintype "passive"))
    )
    (net (code "124") (name "Net-(LED28-RES)") (class "Default")
      (node (ref "LED28") (pin "2") (pinfunction "RES_2") (pintype "passive"))
      (node (ref "U11") (pin "13") (pinfunction "4B_13") (pintype "passive"))
    )
    (net (code "125") (name "Net-(LED29-RES)") (class "Default")
      (node (ref "LED29") (pin "2") (pinfunction "RES_2") (pintype "passive"))
      (node (ref "U12") (pin "13") (pinfunction "4B_13") (pintype "passive"))
    )
    (net (code "126") (name "Net-(LED30-RES)") (class "Default")
      (node (ref "LED30") (pin "2") (pinfunction "RES_2") (pintype "passive"))
      (node (ref "U13") (pin "13") (pinfunction "4B_13") (pintype "passive"))
    )
    (net (code "127") (name "Net-(LED31-RES)") (class "Default")
      (node (ref "LED31") (pin "2") (pinfunction "RES_2") (pintype "passive"))
      (node (ref "U8") (pin "12") (pinfunction "5B_12") (pintype "passive"))
    )
    (net (code "128") (name "Net-(LED32-RES)") (class "Default")
      (node (ref "LED32") (pin "2") (pinfunction "RES_2") (pintype "passive"))
      (node (ref "U9") (pin "12") (pinfunction "5B_12") (pintype "passive"))
    )
    (net (code "129") (name "Net-(LED33-RES)") (class "Default")
      (node (ref "LED33") (pin "2") (pinfunction "RES_2") (pintype "passive"))
      (node (ref "U10") (pin "12") (pinfunction "5B_12") (pintype "passive"))
    )
    (net (code "130") (name "Net-(LED34-RES)") (class "Default")
      (node (ref "LED34") (pin "2") (pinfunction "RES_2") (pintype "passive"))
      (node (ref "U11") (pin "12") (pinfunction "5B_12") (pintype "passive"))
    )
    (net (code "131") (name "Net-(LED35-RES)") (class "Default")
      (node (ref "LED35") (pin "2") (pinfunction "RES_2") (pintype "passive"))
      (node (ref "U12") (pin "12") (pinfunction "5B_12") (pintype "passive"))
    )
    (net (code "132") (name "Net-(LED36-RES)") (class "Default")
      (node (ref "LED36") (pin "2") (pinfunction "RES_2") (pintype "passive"))
      (node (ref "U13") (pin "12") (pinfunction "5B_12") (pintype "passive"))
    )
    (net (code "133") (name "Net-(LED37-A)") (class "Default")
      (node (ref "LED37") (pin "1") (pinfunction "A_1") (pintype "passive"))
      (node (ref "R18") (pin "1") (pinfunction "1_1") (pintype "passive"))
    )
    (net (code "134") (name "Net-(LED38-RES)") (class "Default")
      (node (ref "LED38") (pin "2") (pinfunction "RES_2") (pintype "passive"))
      (node (ref "U8") (pin "11") (pinfunction "6B_11") (pintype "passive"))
    )
    (net (code "135") (name "Net-(LED39-RES)") (class "Default")
      (node (ref "LED39") (pin "2") (pinfunction "RES_2") (pintype "passive"))
      (node (ref "U9") (pin "11") (pinfunction "6B_11") (pintype "passive"))
    )
    (net (code "136") (name "Net-(LED40-RES)") (class "Default")
      (node (ref "LED40") (pin "2") (pinfunction "RES_2") (pintype "passive"))
      (node (ref "U10") (pin "11") (pinfunction "6B_11") (pintype "passive"))
    )
    (net (code "137") (name "Net-(LED41-RES)") (class "Default")
      (node (ref "LED41") (pin "2") (pinfunction "RES_2") (pintype "passive"))
      (node (ref "U11") (pin "11") (pinfunction "6B_11") (pintype "passive"))
    )
    (net (code "138") (name "Net-(LED42-RES)") (class "Default")
      (node (ref "LED42") (pin "2") (pinfunction "RES_2") (pintype "passive"))
      (node (ref "U12") (pin "11") (pinfunction "6B_11") (pintype "passive"))
    )
    (net (code "139") (name "Net-(LED43-RES)") (class "Default")
      (node (ref "LED43") (pin "2") (pinfunction "RES_2") (pintype "passive"))
      (node (ref "U13") (pin "11") (pinfunction "6B_11") (pintype "passive"))
    )
    (net (code "140") (name "Net-(LED44-RES)") (class "Default")
      (node (ref "LED44") (pin "2") (pinfunction "RES_2") (pintype "passive"))
      (node (ref "U8") (pin "10") (pinfunction "7B_10") (pintype "passive"))
    )
    (net (code "141") (name "Net-(LED45-RES)") (class "Default")
      (node (ref "LED45") (pin "2") (pinfunction "RES_2") (pintype "passive"))
      (node (ref "U9") (pin "10") (pinfunction "7B_10") (pintype "passive"))
    )
    (net (code "142") (name "Net-(LED46-RES)") (class "Default")
      (node (ref "LED46") (pin "2") (pinfunction "RES_2") (pintype "passive"))
      (node (ref "U10") (pin "10") (pinfunction "7B_10") (pintype "passive"))
    )
    (net (code "143") (name "Net-(LED47-RES)") (class "Default")
      (node (ref "LED47") (pin "2") (pinfunction "RES_2") (pintype "passive"))
      (node (ref "U11") (pin "10") (pinfunction "7B_10") (pintype "passive"))
    )
    (net (code "144") (name "Net-(LED48-RES)") (class "Default")
      (node (ref "LED48") (pin "2") (pinfunction "RES_2") (pintype "passive"))
      (node (ref "U12") (pin "10") (pinfunction "7B_10") (pintype "passive"))
    )
    (net (code "145") (name "Net-(LED49-RES)") (class "Default")
      (node (ref "LED49") (pin "2") (pinfunction "RES_2") (pintype "passive"))
      (node (ref "U13") (pin "10") (pinfunction "7B_10") (pintype "passive"))
    )
    (net (code "146") (name "Net-(LED50-RES)") (class "Default")
      (node (ref "LED50") (pin "2") (pinfunction "RES_2") (pintype "passive"))
      (node (ref "U8") (pin "9") (pinfunction "8B_9") (pintype "passive"))
    )
    (net (code "147") (name "Net-(LED51-RES)") (class "Default")
      (node (ref "LED51") (pin "2") (pinfunction "RES_2") (pintype "passive"))
      (node (ref "U9") (pin "9") (pinfunction "8B_9") (pintype "passive"))
    )
    (net (code "148") (name "Net-(LED52-RES)") (class "Default")
      (node (ref "LED52") (pin "2") (pinfunction "RES_2") (pintype "passive"))
      (node (ref "U10") (pin "9") (pinfunction "8B_9") (pintype "passive"))
    )
    (net (code "149") (name "Net-(LED53-RES)") (class "Default")
      (node (ref "LED53") (pin "2") (pinfunction "RES_2") (pintype "passive"))
      (node (ref "U11") (pin "9") (pinfunction "8B_9") (pintype "passive"))
    )
    (net (code "150") (name "Net-(LED54-RES)") (class "Default")
      (node (ref "LED54") (pin "2") (pinfunction "RES_2") (pintype "passive"))
      (node (ref "U12") (pin "9") (pinfunction "8B_9") (pintype "passive"))
    )
    (net (code "151") (name "Net-(LED55-RES)") (class "Default")
      (node (ref "LED55") (pin "2") (pinfunction "RES_2") (pintype "passive"))
      (node (ref "U13") (pin "9") (pinfunction "8B_9") (pintype "passive"))
    )
    (net (code "152") (name "Net-(LED56-A)") (class "Default")
      (node (ref "LED56") (pin "1") (pinfunction "A_1") (pintype "passive"))
      (node (ref "R19") (pin "1") (pinfunction "1_1") (pintype "passive"))
    )
    (net (code "153") (name "Net-(LED57-A)") (class "Default")
      (node (ref "LED57") (pin "1") (pinfunction "A_1") (pintype "passive"))
      (node (ref "R20") (pin "1") (pinfunction "1_1") (pintype "passive"))
    )
    (net (code "154") (name "Net-(LED58-A)") (class "Default")
      (node (ref "LED58") (pin "1") (pinfunction "A_1") (pintype "passive"))
      (node (ref "R21") (pin "1") (pinfunction "1_1") (pintype "passive"))
    )
    (net (code "155") (name "Net-(LED59-A)") (class "Default")
      (node (ref "LED59") (pin "1") (pinfunction "A_1") (pintype "passive"))
      (node (ref "R22") (pin "1") (pinfunction "1_1") (pintype "passive"))
    )
    (net (code "156") (name "Net-(LED60-A)") (class "Default")
      (node (ref "LED60") (pin "1") (pinfunction "A_1") (pintype "passive"))
      (node (ref "R23") (pin "1") (pinfunction "1_1") (pintype "passive"))
    )
    (net (code "157") (name "Net-(LED61-A)") (class "Default")
      (node (ref "LED61") (pin "1") (pinfunction "A_1") (pintype "passive"))
      (node (ref "R24") (pin "1") (pinfunction "1_1") (pintype "passive"))
    )
    (net (code "158") (name "Net-(LED62-A)") (class "Default")
      (node (ref "LED62") (pin "1") (pinfunction "A_1") (pintype "passive"))
      (node (ref "R25") (pin "1") (pinfunction "1_1") (pintype "passive"))
    )
    (net (code "159") (name "Net-(LED63-RES)") (class "Default")
      (node (ref "LED63") (pin "2") (pinfunction "RES_2") (pintype "passive"))
      (node (ref "U20") (pin "16") (pinfunction "1B_16") (pintype "passive"))
    )
    (net (code "160") (name "Net-(LED64-RES)") (class "Default")
      (node (ref "LED64") (pin "2") (pinfunction "RES_2") (pintype "passive"))
      (node (ref "U21") (pin "16") (pinfunction "1B_16") (pintype "passive"))
    )
    (net (code "161") (name "Net-(LED65-RES)") (class "Default")
      (node (ref "LED65") (pin "2") (pinfunction "RES_2") (pintype "passive"))
      (node (ref "U22") (pin "16") (pinfunction "1B_16") (pintype "passive"))
    )
    (net (code "162") (name "Net-(LED66-RES)") (class "Default")
      (node (ref "LED66") (pin "2") (pinfunction "RES_2") (pintype "passive"))
      (node (ref "U23") (pin "16") (pinfunction "1B_16") (pintype "passive"))
    )
    (net (code "163") (name "Net-(LED67-RES)") (class "Default")
      (node (ref "LED67") (pin "2") (pinfunction "RES_2") (pintype "passive"))
      (node (ref "U24") (pin "16") (pinfunction "1B_16") (pintype "passive"))
    )
    (net (code "164") (name "Net-(LED68-RES)") (class "Default")
      (node (ref "LED68") (pin "2") (pinfunction "RES_2") (pintype "passive"))
      (node (ref "U25") (pin "16") (pinfunction "1B_16") (pintype "passive"))
    )
    (net (code "165") (name "Net-(LED69-RES)") (class "Default")
      (node (ref "LED69") (pin "2") (pinfunction "RES_2") (pintype "passive"))
      (node (ref "U20") (pin "15") (pinfunction "2B_15") (pintype "passive"))
    )
    (net (code "166") (name "Net-(LED70-RES)") (class "Default")
      (node (ref "LED70") (pin "2") (pinfunction "RES_2") (pintype "passive"))
      (node (ref "U21") (pin "15") (pinfunction "2B_15") (pintype "passive"))
    )
    (net (code "167") (name "Net-(LED71-RES)") (class "Default")
      (node (ref "LED71") (pin "2") (pinfunction "RES_2") (pintype "passive"))
      (node (ref "U22") (pin "15") (pinfunction "2B_15") (pintype "passive"))
    )
    (net (code "168") (name "Net-(LED72-RES)") (class "Default")
      (node (ref "LED72") (pin "2") (pinfunction "RES_2") (pintype "passive"))
      (node (ref "U23") (pin "15") (pinfunction "2B_15") (pintype "passive"))
    )
    (net (code "169") (name "Net-(LED73-RES)") (class "Default")
      (node (ref "LED73") (pin "2") (pinfunction "RES_2") (pintype "passive"))
      (node (ref "U24") (pin "15") (pinfunction "2B_15") (pintype "passive"))
    )
    (net (code "170") (name "Net-(LED74-RES)") (class "Default")
      (node (ref "LED74") (pin "2") (pinfunction "RES_2") (pintype "passive"))
      (node (ref "U25") (pin "15") (pinfunction "2B_15") (pintype "passive"))
    )
    (net (code "171") (name "Net-(LED75-RES)") (class "Default")
      (node (ref "LED75") (pin "2") (pinfunction "RES_2") (pintype "passive"))
      (node (ref "U20") (pin "14") (pinfunction "3B_14") (pintype "passive"))
    )
    (net (code "172") (name "Net-(LED76-RES)") (class "Default")
      (node (ref "LED76") (pin "2") (pinfunction "RES_2") (pintype "passive"))
      (node (ref "U21") (pin "14") (pinfunction "3B_14") (pintype "passive"))
    )
    (net (code "173") (name "Net-(LED77-RES)") (class "Default")
      (node (ref "LED77") (pin "2") (pinfunction "RES_2") (pintype "passive"))
      (node (ref "U22") (pin "14") (pinfunction "3B_14") (pintype "passive"))
    )
    (net (code "174") (name "Net-(LED78-RES)") (class "Default")
      (node (ref "LED78") (pin "2") (pinfunction "RES_2") (pintype "passive"))
      (node (ref "U23") (pin "14") (pinfunction "3B_14") (pintype "passive"))
    )
    (net (code "175") (name "Net-(LED79-RES)") (class "Default")
      (node (ref "LED79") (pin "2") (pinfunction "RES_2") (pintype "passive"))
      (node (ref "U24") (pin "14") (pinfunction "3B_14") (pintype "passive"))
    )
    (net (code "176") (name "Net-(LED80-RES)") (class "Default")
      (node (ref "LED80") (pin "2") (pinfunction "RES_2") (pintype "passive"))
      (node (ref "U25") (pin "14") (pinfunction "3B_14") (pintype "passive"))
    )
    (net (code "177") (name "Net-(LED81-A)") (class "Default")
      (node (ref "LED81") (pin "1") (pinfunction "A_1") (pintype "passive"))
      (node (ref "R26") (pin "1") (pinfunction "1_1") (pintype "passive"))
    )
    (net (code "178") (name "Net-(LED82-RES)") (class "Default")
      (node (ref "LED82") (pin "2") (pinfunction "RES_2") (pintype "passive"))
      (node (ref "U20") (pin "13") (pinfunction "4B_13") (pintype "passive"))
    )
    (net (code "179") (name "Net-(LED83-RES)") (class "Default")
      (node (ref "LED83") (pin "2") (pinfunction "RES_2") (pintype "passive"))
      (node (ref "U21") (pin "13") (pinfunction "4B_13") (pintype "passive"))
    )
    (net (code "180") (name "Net-(LED84-RES)") (class "Default")
      (node (ref "LED84") (pin "2") (pinfunction "RES_2") (pintype "passive"))
      (node (ref "U22") (pin "13") (pinfunction "4B_13") (pintype "passive"))
    )
    (net (code "181") (name "Net-(LED85-RES)") (class "Default")
      (node (ref "LED85") (pin "2") (pinfunction "RES_2") (pintype "passive"))
      (node (ref "U23") (pin "13") (pinfunction "4B_13") (pintype "passive"))
    )
    (net (code "182") (name "Net-(LED86-RES)") (class "Default")
      (node (ref "LED86") (pin "2") (pinfunction "RES_2") (pintype "passive"))
      (node (ref "U24") (pin "13") (pinfunction "4B_13") (pintype "passive"))
    )
    (net (code "183") (name "Net-(LED87-RES)") (class "Default")
      (node (ref "LED87") (pin "2") (pinfunction "RES_2") (pintype "passive"))
      (node (ref "U25") (pin "13") (pinfunction "4B_13") (pintype "passive"))
    )
    (net (code "184") (name "Net-(LED88-RES)") (class "Default")
      (node (ref "LED88") (pin "2") (pinfunction "RES_2") (pintype "passive"))
      (node (ref "U20") (pin "12") (pinfunction "5B_12") (pintype "passive"))
    )
    (net (code "185") (name "Net-(LED89-RES)") (class "Default")
      (node (ref "LED89") (pin "2") (pinfunction "RES_2") (pintype "passive"))
      (node (ref "U11") (pin "16") (pinfunction "1B_16") (pintype "passive"))
    )
    (net (code "186") (name "Net-(LED90-RES)") (class "Default")
      (node (ref "LED90") (pin "2") (pinfunction "RES_2") (pintype "passive"))
      (node (ref "U22") (pin "12") (pinfunction "5B_12") (pintype "passive"))
    )
    (net (code "187") (name "Net-(LED91-RES)") (class "Default")
      (node (ref "LED91") (pin "2") (pinfunction "RES_2") (pintype "passive"))
      (node (ref "U23") (pin "12") (pinfunction "5B_12") (pintype "passive"))
    )
    (net (code "188") (name "Net-(LED92-RES)") (class "Default")
      (node (ref "LED92") (pin "2") (pinfunction "RES_2") (pintype "passive"))
      (node (ref "U24") (pin "12") (pinfunction "5B_12") (pintype "passive"))
    )
    (net (code "189") (name "Net-(LED93-RES)") (class "Default")
      (node (ref "LED93") (pin "2") (pinfunction "RES_2") (pintype "passive"))
      (node (ref "U25") (pin "12") (pinfunction "5B_12") (pintype "passive"))
    )
    (net (code "190") (name "Net-(LED94-RES)") (class "Default")
      (node (ref "LED94") (pin "2") (pinfunction "RES_2") (pintype "passive"))
      (node (ref "U20") (pin "11") (pinfunction "6B_11") (pintype "passive"))
    )
    (net (code "191") (name "Net-(LED95-RES)") (class "Default")
      (node (ref "LED95") (pin "2") (pinfunction "RES_2") (pintype "passive"))
      (node (ref "U11") (pin "15") (pinfunction "2B_15") (pintype "passive"))
    )
    (net (code "192") (name "Net-(LED96-RES)") (class "Default")
      (node (ref "LED96") (pin "2") (pinfunction "RES_2") (pintype "passive"))
      (node (ref "U22") (pin "11") (pinfunction "6B_11") (pintype "passive"))
    )
    (net (code "193") (name "Net-(LED97-RES)") (class "Default")
      (node (ref "LED97") (pin "2") (pinfunction "RES_2") (pintype "passive"))
      (node (ref "U23") (pin "11") (pinfunction "6B_11") (pintype "passive"))
    )
    (net (code "194") (name "Net-(LED98-RES)") (class "Default")
      (node (ref "LED98") (pin "2") (pinfunction "RES_2") (pintype "passive"))
      (node (ref "U24") (pin "11") (pinfunction "6B_11") (pintype "passive"))
    )
    (net (code "195") (name "Net-(LED99-RES)") (class "Default")
      (node (ref "LED99") (pin "2") (pinfunction "RES_2") (pintype "passive"))
      (node (ref "U25") (pin "11") (pinfunction "6B_11") (pintype "passive"))
    )
    (net (code "196") (name "Net-(LED100-A)") (class "Default")
      (node (ref "LED100") (pin "1") (pinfunction "A_1") (pintype "passive"))
      (node (ref "R27") (pin "1") (pinfunction "1_1") (pintype "passive"))
    )
    (net (code "197") (name "Net-(LED101-RES)") (class "Default")
      (node (ref "LED101") (pin "2") (pinfunction "RES_2") (pintype "passive"))
      (node (ref "U20") (pin "10") (pinfunction "7B_10") (pintype "passive"))
    )
    (net (code "198") (name "Net-(LED102-RES)") (class "Default")
      (node (ref "LED102") (pin "2") (pinfunction "RES_2") (pintype "passive"))
      (node (ref "U21") (pin "10") (pinfunction "7B_10") (pintype "passive"))
    )
    (net (code "199") (name "Net-(LED103-RES)") (class "Default")
      (node (ref "LED103") (pin "2") (pinfunction "RES_2") (pintype "passive"))
      (node (ref "U22") (pin "10") (pinfunction "7B_10") (pintype "passive"))
    )
    (net (code "200") (name "Net-(LED104-RES)") (class "Default")
      (node (ref "LED104") (pin "2") (pinfunction "RES_2") (pintype "passive"))
      (node (ref "U23") (pin "10") (pinfunction "7B_10") (pintype "passive"))
    )
    (net (code "201") (name "Net-(LED105-RES)") (class "Default")
      (node (ref "LED105") (pin "2") (pinfunction "RES_2") (pintype "passive"))
      (node (ref "U24") (pin "10") (pinfunction "7B_10") (pintype "passive"))
    )
    (net (code "202") (name "Net-(LED106-RES)") (class "Default")
      (node (ref "LED106") (pin "2") (pinfunction "RES_2") (pintype "passive"))
      (node (ref "U25") (pin "10") (pinfunction "7B_10") (pintype "passive"))
    )
    (net (code "203") (name "Net-(LED107-RES)") (class "Default")
      (node (ref "LED107") (pin "2") (pinfunction "RES_2") (pintype "passive"))
      (node (ref "U20") (pin "9") (pinfunction "8B_9") (pintype "passive"))
    )
    (net (code "204") (name "Net-(LED108-RES)") (class "Default")
      (node (ref "LED108") (pin "2") (pinfunction "RES_2") (pintype "passive"))
      (node (ref "U21") (pin "9") (pinfunction "8B_9") (pintype "passive"))
    )
    (net (code "205") (name "Net-(LED109-RES)") (class "Default")
      (node (ref "LED109") (pin "2") (pinfunction "RES_2") (pintype "passive"))
      (node (ref "U22") (pin "9") (pinfunction "8B_9") (pintype "passive"))
    )
    (net (code "206") (name "Net-(LED111-RES)") (class "Default")
      (node (ref "LED111") (pin "2") (pinfunction "RES_2") (pintype "passive"))
      (node (ref "U24") (pin "9") (pinfunction "8B_9") (pintype "passive"))
    )
    (net (code "207") (name "Net-(LED112-RES)") (class "Default")
      (node (ref "LED112") (pin "2") (pinfunction "RES_2") (pintype "passive"))
      (node (ref "U25") (pin "9") (pinfunction "8B_9") (pintype "passive"))
    )
    (net (code "208") (name "Net-(U2-Y1)") (class "Default")
      (node (ref "U2") (pin "18") (pinfunction "Y1_18") (pintype "tri_state"))
      (node (ref "U8") (pin "1") (pinfunction "1A_1") (pintype "passive"))
    )
    (net (code "209") (name "Net-(U2-Y2)") (class "Default")
      (node (ref "U2") (pin "17") (pinfunction "Y2_17") (pintype "tri_state"))
      (node (ref "U8") (pin "2") (pinfunction "2A_2") (pintype "passive"))
    )
    (net (code "210") (name "Net-(U2-Y3)") (class "Default")
      (node (ref "U2") (pin "16") (pinfunction "Y3_16") (pintype "tri_state"))
      (node (ref "U8") (pin "3") (pinfunction "3A_3") (pintype "passive"))
    )
    (net (code "211") (name "Net-(U2-Y4)") (class "Default")
      (node (ref "U2") (pin "15") (pinfunction "Y4_15") (pintype "tri_state"))
      (node (ref "U8") (pin "4") (pinfunction "4A_4") (pintype "passive"))
    )
    (net (code "212") (name "Net-(U2-Y5)") (class "Default")
      (node (ref "U2") (pin "14") (pinfunction "Y5_14") (pintype "tri_state"))
      (node (ref "U8") (pin "5") (pinfunction "5A_5") (pintype "passive"))
    )
    (net (code "213") (name "Net-(U2-Y6)") (class "Default")
      (node (ref "U2") (pin "13") (pinfunction "Y6_13") (pintype "tri_state"))
      (node (ref "U8") (pin "6") (pinfunction "6A_6") (pintype "passive"))
    )
    (net (code "214") (name "Net-(U2-Y7)") (class "Default")
      (node (ref "U2") (pin "12") (pinfunction "Y7_12") (pintype "tri_state"))
      (node (ref "U8") (pin "7") (pinfunction "7A_7") (pintype "passive"))
    )
    (net (code "215") (name "Net-(U2-Y8)") (class "Default")
      (node (ref "U2") (pin "11") (pinfunction "Y8_11") (pintype "tri_state"))
      (node (ref "U8") (pin "8") (pinfunction "8A_8") (pintype "passive"))
    )
    (net (code "216") (name "Net-(U3-Y1)") (class "Default")
      (node (ref "U3") (pin "18") (pinfunction "Y1_18") (pintype "tri_state"))
      (node (ref "U9") (pin "1") (pinfunction "1A_1") (pintype "passive"))
    )
    (net (code "217") (name "Net-(U3-Y2)") (class "Default")
      (node (ref "U3") (pin "17") (pinfunction "Y2_17") (pintype "tri_state"))
      (node (ref "U9") (pin "2") (pinfunction "2A_2") (pintype "passive"))
    )
    (net (code "218") (name "Net-(U3-Y3)") (class "Default")
      (node (ref "U3") (pin "16") (pinfunction "Y3_16") (pintype "tri_state"))
      (node (ref "U9") (pin "3") (pinfunction "3A_3") (pintype "passive"))
    )
    (net (code "219") (name "Net-(U3-Y4)") (class "Default")
      (node (ref "U3") (pin "15") (pinfunction "Y4_15") (pintype "tri_state"))
      (node (ref "U9") (pin "4") (pinfunction "4A_4") (pintype "passive"))
    )
    (net (code "220") (name "Net-(U3-Y5)") (class "Default")
      (node (ref "U3") (pin "14") (pinfunction "Y5_14") (pintype "tri_state"))
      (node (ref "U9") (pin "5") (pinfunction "5A_5") (pintype "passive"))
    )
    (net (code "221") (name "Net-(U3-Y6)") (class "Default")
      (node (ref "U3") (pin "13") (pinfunction "Y6_13") (pintype "tri_state"))
      (node (ref "U9") (pin "6") (pinfunction "6A_6") (pintype "passive"))
    )
    (net (code "222") (name "Net-(U3-Y7)") (class "Default")
      (node (ref "U3") (pin "12") (pinfunction "Y7_12") (pintype "tri_state"))
      (node (ref "U9") (pin "7") (pinfunction "7A_7") (pintype "passive"))
    )
    (net (code "223") (name "Net-(U3-Y8)") (class "Default")
      (node (ref "U3") (pin "11") (pinfunction "Y8_11") (pintype "tri_state"))
      (node (ref "U9") (pin "8") (pinfunction "8A_8") (pintype "passive"))
    )
    (net (code "224") (name "Net-(U10-1A)") (class "Default")
      (node (ref "U10") (pin "1") (pinfunction "1A_1") (pintype "passive"))
      (node (ref "U4") (pin "18") (pinfunction "Y1_18") (pintype "tri_state"))
    )
    (net (code "225") (name "Net-(U10-2A)") (class "Default")
      (node (ref "U10") (pin "2") (pinfunction "2A_2") (pintype "passive"))
      (node (ref "U4") (pin "17") (pinfunction "Y2_17") (pintype "tri_state"))
    )
    (net (code "226") (name "Net-(U10-3A)") (class "Default")
      (node (ref "U10") (pin "3") (pinfunction "3A_3") (pintype "passive"))
      (node (ref "U4") (pin "16") (pinfunction "Y3_16") (pintype "tri_state"))
    )
    (net (code "227") (name "Net-(U10-4A)") (class "Default")
      (node (ref "U10") (pin "4") (pinfunction "4A_4") (pintype "passive"))
      (node (ref "U4") (pin "15") (pinfunction "Y4_15") (pintype "tri_state"))
    )
    (net (code "228") (name "Net-(U10-5A)") (class "Default")
      (node (ref "U10") (pin "5") (pinfunction "5A_5") (pintype "passive"))
      (node (ref "U4") (pin "14") (pinfunction "Y5_14") (pintype "tri_state"))
    )
    (net (code "229") (name "Net-(U10-6A)") (class "Default")
      (node (ref "U10") (pin "6") (pinfunction "6A_6") (pintype "passive"))
      (node (ref "U4") (pin "13") (pinfunction "Y6_13") (pintype "tri_state"))
    )
    (net (code "230") (name "Net-(U10-7A)") (class "Default")
      (node (ref "U10") (pin "7") (pinfunction "7A_7") (pintype "passive"))
      (node (ref "U4") (pin "12") (pinfunction "Y7_12") (pintype "tri_state"))
    )
    (net (code "231") (name "Net-(U10-8A)") (class "Default")
      (node (ref "U10") (pin "8") (pinfunction "8A_8") (pintype "passive"))
      (node (ref "U4") (pin "11") (pinfunction "Y8_11") (pintype "tri_state"))
    )
    (net (code "232") (name "Net-(U11-1A)") (class "Default")
      (node (ref "U11") (pin "1") (pinfunction "1A_1") (pintype "passive"))
      (node (ref "U5") (pin "18") (pinfunction "Y1_18") (pintype "tri_state"))
    )
    (net (code "233") (name "Net-(U11-2A)") (class "Default")
      (node (ref "U11") (pin "2") (pinfunction "2A_2") (pintype "passive"))
      (node (ref "U5") (pin "17") (pinfunction "Y2_17") (pintype "tri_state"))
    )
    (net (code "234") (name "Net-(U11-3A)") (class "Default")
      (node (ref "U11") (pin "3") (pinfunction "3A_3") (pintype "passive"))
      (node (ref "U5") (pin "16") (pinfunction "Y3_16") (pintype "tri_state"))
    )
    (net (code "235") (name "Net-(U11-4A)") (class "Default")
      (node (ref "U11") (pin "4") (pinfunction "4A_4") (pintype "passive"))
      (node (ref "U5") (pin "15") (pinfunction "Y4_15") (pintype "tri_state"))
    )
    (net (code "236") (name "Net-(U11-5A)") (class "Default")
      (node (ref "U11") (pin "5") (pinfunction "5A_5") (pintype "passive"))
      (node (ref "U5") (pin "14") (pinfunction "Y5_14") (pintype "tri_state"))
    )
    (net (code "237") (name "Net-(U11-6A)") (class "Default")
      (node (ref "U11") (pin "6") (pinfunction "6A_6") (pintype "passive"))
      (node (ref "U5") (pin "13") (pinfunction "Y6_13") (pintype "tri_state"))
    )
    (net (code "238") (name "Net-(U11-7A)") (class "Default")
      (node (ref "U11") (pin "7") (pinfunction "7A_7") (pintype "passive"))
      (node (ref "U5") (pin "12") (pinfunction "Y7_12") (pintype "tri_state"))
    )
    (net (code "239") (name "Net-(U11-8A)") (class "Default")
      (node (ref "U11") (pin "8") (pinfunction "8A_8") (pintype "passive"))
      (node (ref "U5") (pin "11") (pinfunction "Y8_11") (pintype "tri_state"))
    )
    (net (code "240") (name "Net-(U12-1A)") (class "Default")
      (node (ref "U12") (pin "1") (pinfunction "1A_1") (pintype "passive"))
      (node (ref "U6") (pin "18") (pinfunction "Y1_18") (pintype "tri_state"))
    )
    (net (code "241") (name "Net-(U12-2A)") (class "Default")
      (node (ref "U12") (pin "2") (pinfunction "2A_2") (pintype "passive"))
      (node (ref "U6") (pin "17") (pinfunction "Y2_17") (pintype "tri_state"))
    )
    (net (code "242") (name "Net-(U12-3A)") (class "Default")
      (node (ref "U12") (pin "3") (pinfunction "3A_3") (pintype "passive"))
      (node (ref "U6") (pin "16") (pinfunction "Y3_16") (pintype "tri_state"))
    )
    (net (code "243") (name "Net-(U12-4A)") (class "Default")
      (node (ref "U12") (pin "4") (pinfunction "4A_4") (pintype "passive"))
      (node (ref "U6") (pin "15") (pinfunction "Y4_15") (pintype "tri_state"))
    )
    (net (code "244") (name "Net-(U12-5A)") (class "Default")
      (node (ref "U12") (pin "5") (pinfunction "5A_5") (pintype "passive"))
      (node (ref "U6") (pin "14") (pinfunction "Y5_14") (pintype "tri_state"))
    )
    (net (code "245") (name "Net-(U12-6A)") (class "Default")
      (node (ref "U12") (pin "6") (pinfunction "6A_6") (pintype "passive"))
      (node (ref "U6") (pin "13") (pinfunction "Y6_13") (pintype "tri_state"))
    )
    (net (code "246") (name "Net-(U12-7A)") (class "Default")
      (node (ref "U12") (pin "7") (pinfunction "7A_7") (pintype "passive"))
      (node (ref "U6") (pin "12") (pinfunction "Y7_12") (pintype "tri_state"))
    )
    (net (code "247") (name "Net-(U12-8A)") (class "Default")
      (node (ref "U12") (pin "8") (pinfunction "8A_8") (pintype "passive"))
      (node (ref "U6") (pin "11") (pinfunction "Y8_11") (pintype "tri_state"))
    )
    (net (code "248") (name "Net-(U13-1A)") (class "Default")
      (node (ref "U13") (pin "1") (pinfunction "1A_1") (pintype "passive"))
      (node (ref "U7") (pin "18") (pinfunction "Y1_18") (pintype "tri_state"))
    )
    (net (code "249") (name "Net-(U13-2A)") (class "Default")
      (node (ref "U13") (pin "2") (pinfunction "2A_2") (pintype "passive"))
      (node (ref "U7") (pin "17") (pinfunction "Y2_17") (pintype "tri_state"))
    )
    (net (code "250") (name "Net-(U13-3A)") (class "Default")
      (node (ref "U13") (pin "3") (pinfunction "3A_3") (pintype "passive"))
      (node (ref "U7") (pin "16") (pinfunction "Y3_16") (pintype "tri_state"))
    )
    (net (code "251") (name "Net-(U13-4A)") (class "Default")
      (node (ref "U13") (pin "4") (pinfunction "4A_4") (pintype "passive"))
      (node (ref "U7") (pin "15") (pinfunction "Y4_15") (pintype "tri_state"))
    )
    (net (code "252") (name "Net-(U13-5A)") (class "Default")
      (node (ref "U13") (pin "5") (pinfunction "5A_5") (pintype "passive"))
      (node (ref "U7") (pin "14") (pinfunction "Y5_14") (pintype "tri_state"))
    )
    (net (code "253") (name "Net-(U13-6A)") (class "Default")
      (node (ref "U13") (pin "6") (pinfunction "6A_6") (pintype "passive"))
      (node (ref "U7") (pin "13") (pinfunction "Y6_13") (pintype "tri_state"))
    )
    (net (code "254") (name "Net-(U13-7A)") (class "Default")
      (node (ref "U13") (pin "7") (pinfunction "7A_7") (pintype "passive"))
      (node (ref "U7") (pin "12") (pinfunction "Y7_12") (pintype "tri_state"))
    )
    (net (code "255") (name "Net-(U13-8A)") (class "Default")
      (node (ref "U13") (pin "8") (pinfunction "8A_8") (pintype "passive"))
      (node (ref "U7") (pin "11") (pinfunction "Y8_11") (pintype "tri_state"))
    )
    (net (code "256") (name "Net-(U14-Y1)") (class "Default")
      (node (ref "U14") (pin "18") (pinfunction "Y1_18") (pintype "tri_state"))
      (node (ref "U20") (pin "1") (pinfunction "1A_1") (pintype "passive"))
    )
    (net (code "257") (name "Net-(U14-Y2)") (class "Default")
      (node (ref "U14") (pin "17") (pinfunction "Y2_17") (pintype "tri_state"))
      (node (ref "U20") (pin "2") (pinfunction "2A_2") (pintype "passive"))
    )
    (net (code "258") (name "Net-(U14-Y3)") (class "Default")
      (node (ref "U14") (pin "16") (pinfunction "Y3_16") (pintype "tri_state"))
      (node (ref "U20") (pin "3") (pinfunction "3A_3") (pintype "passive"))
    )
    (net (code "259") (name "Net-(U14-Y4)") (class "Default")
      (node (ref "U14") (pin "15") (pinfunction "Y4_15") (pintype "tri_state"))
      (node (ref "U20") (pin "4") (pinfunction "4A_4") (pintype "passive"))
    )
    (net (code "260") (name "Net-(U14-Y5)") (class "Default")
      (node (ref "U14") (pin "14") (pinfunction "Y5_14") (pintype "tri_state"))
      (node (ref "U20") (pin "5") (pinfunction "5A_5") (pintype "passive"))
    )
    (net (code "261") (name "Net-(U14-Y6)") (class "Default")
      (node (ref "U14") (pin "13") (pinfunction "Y6_13") (pintype "tri_state"))
      (node (ref "U20") (pin "6") (pinfunction "6A_6") (pintype "passive"))
    )
    (net (code "262") (name "Net-(U14-Y7)") (class "Default")
      (node (ref "U14") (pin "12") (pinfunction "Y7_12") (pintype "tri_state"))
      (node (ref "U20") (pin "7") (pinfunction "7A_7") (pintype "passive"))
    )
    (net (code "263") (name "Net-(U14-Y8)") (class "Default")
      (node (ref "U14") (pin "11") (pinfunction "Y8_11") (pintype "tri_state"))
      (node (ref "U20") (pin "8") (pinfunction "8A_8") (pintype "passive"))
    )
    (net (code "264") (name "Net-(U15-Y1)") (class "Default")
      (node (ref "U15") (pin "18") (pinfunction "Y1_18") (pintype "tri_state"))
      (node (ref "U21") (pin "1") (pinfunction "1A_1") (pintype "passive"))
    )
    (net (code "265") (name "Net-(U15-Y2)") (class "Default")
      (node (ref "U15") (pin "17") (pinfunction "Y2_17") (pintype "tri_state"))
      (node (ref "U21") (pin "2") (pinfunction "2A_2") (pintype "passive"))
    )
    (net (code "266") (name "Net-(U15-Y3)") (class "Default")
      (node (ref "U15") (pin "16") (pinfunction "Y3_16") (pintype "tri_state"))
      (node (ref "U21") (pin "3") (pinfunction "3A_3") (pintype "passive"))
    )
    (net (code "267") (name "Net-(U15-Y4)") (class "Default")
      (node (ref "U15") (pin "15") (pinfunction "Y4_15") (pintype "tri_state"))
      (node (ref "U21") (pin "4") (pinfunction "4A_4") (pintype "passive"))
    )
    (net (code "268") (name "Net-(U15-Y5)") (class "Default")
      (node (ref "U15") (pin "14") (pinfunction "Y5_14") (pintype "tri_state"))
      (node (ref "U21") (pin "5") (pinfunction "5A_5") (pintype "passive"))
    )
    (net (code "269") (name "Net-(U15-Y6)") (class "Default")
      (node (ref "U15") (pin "13") (pinfunction "Y6_13") (pintype "tri_state"))
      (node (ref "U21") (pin "6") (pinfunction "6A_6") (pintype "passive"))
    )
    (net (code "270") (name "Net-(U15-Y7)") (class "Default")
      (node (ref "U15") (pin "12") (pinfunction "Y7_12") (pintype "tri_state"))
      (node (ref "U21") (pin "7") (pinfunction "7A_7") (pintype "passive"))
    )
    (net (code "271") (name "Net-(U15-Y8)") (class "Default")
      (node (ref "U15") (pin "11") (pinfunction "Y8_11") (pintype "tri_state"))
      (node (ref "U21") (pin "8") (pinfunction "8A_8") (pintype "passive"))
    )
    (net (code "272") (name "Net-(U16-Y1)") (class "Default")
      (node (ref "U16") (pin "18") (pinfunction "Y1_18") (pintype "tri_state"))
      (node (ref "U22") (pin "1") (pinfunction "1A_1") (pintype "passive"))
    )
    (net (code "273") (name "Net-(U16-Y2)") (class "Default")
      (node (ref "U16") (pin "17") (pinfunction "Y2_17") (pintype "tri_state"))
      (node (ref "U22") (pin "2") (pinfunction "2A_2") (pintype "passive"))
    )
    (net (code "274") (name "Net-(U16-Y3)") (class "Default")
      (node (ref "U16") (pin "16") (pinfunction "Y3_16") (pintype "tri_state"))
      (node (ref "U22") (pin "3") (pinfunction "3A_3") (pintype "passive"))
    )
    (net (code "275") (name "Net-(U16-Y4)") (class "Default")
      (node (ref "U16") (pin "15") (pinfunction "Y4_15") (pintype "tri_state"))
      (node (ref "U22") (pin "4") (pinfunction "4A_4") (pintype "passive"))
    )
    (net (code "276") (name "Net-(U16-Y5)") (class "Default")
      (node (ref "U16") (pin "14") (pinfunction "Y5_14") (pintype "tri_state"))
      (node (ref "U22") (pin "5") (pinfunction "5A_5") (pintype "passive"))
    )
    (net (code "277") (name "Net-(U16-Y6)") (class "Default")
      (node (ref "U16") (pin "13") (pinfunction "Y6_13") (pintype "tri_state"))
      (node (ref "U22") (pin "6") (pinfunction "6A_6") (pintype "passive"))
    )
    (net (code "278") (name "Net-(U16-Y7)") (class "Default")
      (node (ref "U16") (pin "12") (pinfunction "Y7_12") (pintype "tri_state"))
      (node (ref "U22") (pin "7") (pinfunction "7A_7") (pintype "passive"))
    )
    (net (code "279") (name "Net-(U16-Y8)") (class "Default")
      (node (ref "U16") (pin "11") (pinfunction "Y8_11") (pintype "tri_state"))
      (node (ref "U22") (pin "8") (pinfunction "8A_8") (pintype "passive"))
    )
    (net (code "280") (name "Net-(U17-Y1)") (class "Default")
      (node (ref "U17") (pin "18") (pinfunction "Y1_18") (pintype "tri_state"))
      (node (ref "U23") (pin "1") (pinfunction "1A_1") (pintype "passive"))
    )
    (net (code "281") (name "Net-(U17-Y2)") (class "Default")
      (node (ref "U17") (pin "17") (pinfunction "Y2_17") (pintype "tri_state"))
      (node (ref "U23") (pin "2") (pinfunction "2A_2") (pintype "passive"))
    )
    (net (code "282") (name "Net-(U17-Y3)") (class "Default")
      (node (ref "U17") (pin "16") (pinfunction "Y3_16") (pintype "tri_state"))
      (node (ref "U23") (pin "3") (pinfunction "3A_3") (pintype "passive"))
    )
    (net (code "283") (name "Net-(U17-Y4)") (class "Default")
      (node (ref "U17") (pin "15") (pinfunction "Y4_15") (pintype "tri_state"))
      (node (ref "U23") (pin "4") (pinfunction "4A_4") (pintype "passive"))
    )
    (net (code "284") (name "Net-(U17-Y5)") (class "Default")
      (node (ref "U17") (pin "14") (pinfunction "Y5_14") (pintype "tri_state"))
      (node (ref "U23") (pin "5") (pinfunction "5A_5") (pintype "passive"))
    )
    (net (code "285") (name "Net-(U17-Y6)") (class "Default")
      (node (ref "U17") (pin "13") (pinfunction "Y6_13") (pintype "tri_state"))
      (node (ref "U23") (pin "6") (pinfunction "6A_6") (pintype "passive"))
    )
    (net (code "286") (name "Net-(U17-Y7)") (class "Default")
      (node (ref "U17") (pin "12") (pinfunction "Y7_12") (pintype "tri_state"))
      (node (ref "U23") (pin "7") (pinfunction "7A_7") (pintype "passive"))
    )
    (net (code "287") (name "Net-(U17-Y8)") (class "Default")
      (node (ref "U17") (pin "11") (pinfunction "Y8_11") (pintype "tri_state"))
      (node (ref "U23") (pin "8") (pinfunction "8A_8") (pintype "passive"))
    )
    (net (code "288") (name "Net-(U18-A1)") (class "Default")
      (node (ref "J35") (pin "1") (pinfunction "1_1") (pintype "passive"))
      (node (ref "U18") (pin "2") (pinfunction "A1_2") (pintype "input"))
    )
    (net (code "289") (name "Net-(U18-A2)") (class "Default")
      (node (ref "J35") (pin "2") (pinfunction "2_2") (pintype "passive"))
      (node (ref "U18") (pin "3") (pinfunction "A2_3") (pintype "input"))
    )
    (net (code "290") (name "Net-(U18-A3)") (class "Default")
      (node (ref "J35") (pin "3") (pinfunction "3_3") (pintype "passive"))
      (node (ref "U18") (pin "4") (pinfunction "A3_4") (pintype "input"))
    )
    (net (code "291") (name "Net-(U18-A4)") (class "Default")
      (node (ref "J35") (pin "4") (pinfunction "4_4") (pintype "passive"))
      (node (ref "U18") (pin "5") (pinfunction "A4_5") (pintype "input"))
    )
    (net (code "292") (name "Net-(U18-A5)") (class "Default")
      (node (ref "J35") (pin "5") (pinfunction "5_5") (pintype "passive"))
      (node (ref "U18") (pin "6") (pinfunction "A5_6") (pintype "input"))
    )
    (net (code "293") (name "Net-(U18-A6)") (class "Default")
      (node (ref "J35") (pin "6") (pinfunction "6_6") (pintype "passive"))
      (node (ref "U18") (pin "7") (pinfunction "A6_7") (pintype "input"))
    )
    (net (code "294") (name "Net-(U18-A7)") (class "Default")
      (node (ref "J35") (pin "7") (pinfunction "7_7") (pintype "passive"))
      (node (ref "U18") (pin "8") (pinfunction "A7_8") (pintype "input"))
    )
    (net (code "295") (name "Net-(U18-A8)") (class "Default")
      (node (ref "J35") (pin "8") (pinfunction "8_8") (pintype "passive"))
      (node (ref "U18") (pin "9") (pinfunction "A8_9") (pintype "input"))
    )
    (net (code "296") (name "Net-(U18-Y1)") (class "Default")
      (node (ref "U18") (pin "18") (pinfunction "Y1_18") (pintype "tri_state"))
      (node (ref "U24") (pin "1") (pinfunction "1A_1") (pintype "passive"))
    )
    (net (code "297") (name "Net-(U18-Y2)") (class "Default")
      (node (ref "U18") (pin "17") (pinfunction "Y2_17") (pintype "tri_state"))
      (node (ref "U24") (pin "2") (pinfunction "2A_2") (pintype "passive"))
    )
    (net (code "298") (name "Net-(U18-Y3)") (class "Default")
      (node (ref "U18") (pin "16") (pinfunction "Y3_16") (pintype "tri_state"))
      (node (ref "U24") (pin "3") (pinfunction "3A_3") (pintype "passive"))
    )
    (net (code "299") (name "Net-(U18-Y4)") (class "Default")
      (node (ref "U18") (pin "15") (pinfunction "Y4_15") (pintype "tri_state"))
      (node (ref "U24") (pin "4") (pinfunction "4A_4") (pintype "passive"))
    )
    (net (code "300") (name "Net-(U18-Y5)") (class "Default")
      (node (ref "U18") (pin "14") (pinfunction "Y5_14") (pintype "tri_state"))
      (node (ref "U24") (pin "5") (pinfunction "5A_5") (pintype "passive"))
    )
    (net (code "301") (name "Net-(U18-Y6)") (class "Default")
      (node (ref "U18") (pin "13") (pinfunction "Y6_13") (pintype "tri_state"))
      (node (ref "U24") (pin "6") (pinfunction "6A_6") (pintype "passive"))
    )
    (net (code "302") (name "Net-(U18-Y7)") (class "Default")
      (node (ref "U18") (pin "12") (pinfunction "Y7_12") (pintype "tri_state"))
      (node (ref "U24") (pin "7") (pinfunction "7A_7") (pintype "passive"))
    )
    (net (code "303") (name "Net-(U18-Y8)") (class "Default")
      (node (ref "U18") (pin "11") (pinfunction "Y8_11") (pintype "tri_state"))
      (node (ref "U24") (pin "8") (pinfunction "8A_8") (pintype "passive"))
    )
    (net (code "304") (name "Net-(U19-A1)") (class "Default")
      (node (ref "J36") (pin "1") (pinfunction "1_1") (pintype "passive"))
      (node (ref "U19") (pin "2") (pinfunction "A1_2") (pintype "input"))
    )
    (net (code "305") (name "Net-(U19-A2)") (class "Default")
      (node (ref "J36") (pin "2") (pinfunction "2_2") (pintype "passive"))
      (node (ref "U19") (pin "3") (pinfunction "A2_3") (pintype "input"))
    )
    (net (code "306") (name "Net-(U19-A3)") (class "Default")
      (node (ref "J36") (pin "3") (pinfunction "3_3") (pintype "passive"))
      (node (ref "U19") (pin "4") (pinfunction "A3_4") (pintype "input"))
    )
    (net (code "307") (name "Net-(U19-A4)") (class "Default")
      (node (ref "J36") (pin "4") (pinfunction "4_4") (pintype "passive"))
      (node (ref "U19") (pin "5") (pinfunction "A4_5") (pintype "input"))
    )
    (net (code "308") (name "Net-(U19-A5)") (class "Default")
      (node (ref "J36") (pin "5") (pinfunction "5_5") (pintype "passive"))
      (node (ref "U19") (pin "6") (pinfunction "A5_6") (pintype "input"))
    )
    (net (code "309") (name "Net-(U19-A6)") (class "Default")
      (node (ref "J36") (pin "6") (pinfunction "6_6") (pintype "passive"))
      (node (ref "U19") (pin "7") (pinfunction "A6_7") (pintype "input"))
    )
    (net (code "310") (name "Net-(U19-A7)") (class "Default")
      (node (ref "J36") (pin "7") (pinfunction "7_7") (pintype "passive"))
      (node (ref "U19") (pin "8") (pinfunction "A7_8") (pintype "input"))
    )
    (net (code "311") (name "Net-(U19-A8)") (class "Default")
      (node (ref "J36") (pin "8") (pinfunction "8_8") (pintype "passive"))
      (node (ref "U19") (pin "9") (pinfunction "A8_9") (pintype "input"))
    )
    (net (code "312") (name "Net-(U19-Y1)") (class "Default")
      (node (ref "U19") (pin "18") (pinfunction "Y1_18") (pintype "tri_state"))
      (node (ref "U25") (pin "1") (pinfunction "1A_1") (pintype "passive"))
    )
    (net (code "313") (name "Net-(U19-Y2)") (class "Default")
      (node (ref "U19") (pin "17") (pinfunction "Y2_17") (pintype "tri_state"))
      (node (ref "U25") (pin "2") (pinfunction "2A_2") (pintype "passive"))
    )
    (net (code "314") (name "Net-(U19-Y3)") (class "Default")
      (node (ref "U19") (pin "16") (pinfunction "Y3_16") (pintype "tri_state"))
      (node (ref "U25") (pin "3") (pinfunction "3A_3") (pintype "passive"))
    )
    (net (code "315") (name "Net-(U19-Y4)") (class "Default")
      (node (ref "U19") (pin "15") (pinfunction "Y4_15") (pintype "tri_state"))
      (node (ref "U25") (pin "4") (pinfunction "4A_4") (pintype "passive"))
    )
    (net (code "316") (name "Net-(U19-Y5)") (class "Default")
      (node (ref "U19") (pin "14") (pinfunction "Y5_14") (pintype "tri_state"))
      (node (ref "U25") (pin "5") (pinfunction "5A_5") (pintype "passive"))
    )
    (net (code "317") (name "Net-(U19-Y6)") (class "Default")
      (node (ref "U19") (pin "13") (pinfunction "Y6_13") (pintype "tri_state"))
      (node (ref "U25") (pin "6") (pinfunction "6A_6") (pintype "passive"))
    )
    (net (code "318") (name "Net-(U19-Y7)") (class "Default")
      (node (ref "U19") (pin "12") (pinfunction "Y7_12") (pintype "tri_state"))
      (node (ref "U25") (pin "7") (pinfunction "7A_7") (pintype "passive"))
    )
    (net (code "319") (name "Net-(U19-Y8)") (class "Default")
      (node (ref "U19") (pin "11") (pinfunction "Y8_11") (pintype "tri_state"))
      (node (ref "U25") (pin "8") (pinfunction "8A_8") (pintype "passive"))
    )
    (net (code "320") (name "unconnected-(U17-A8-Pad9)") (class "Default")
      (node (ref "U17") (pin "9") (pinfunction "A8_9") (pintype "input+no_connect"))
    )
    (net (code "321") (name "unconnected-(U19-GND-Pad10)") (class "Default")
      (node (ref "U19") (pin "10") (pinfunction "GND_10") (pintype "power_in"))
    )
    (net (code "322") (name "unconnected-(U23-8B-Pad9)") (class "Default")
      (node (ref "U23") (pin "9") (pinfunction "8B_9") (pintype "passive+no_connect"))
    )
  )
)
